# interface.net
KiCad netlist of a schematic drawn in Altium Designer
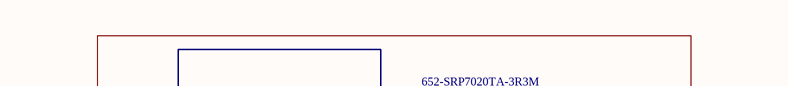
[diagram p0: interface.SchDoc, top left]
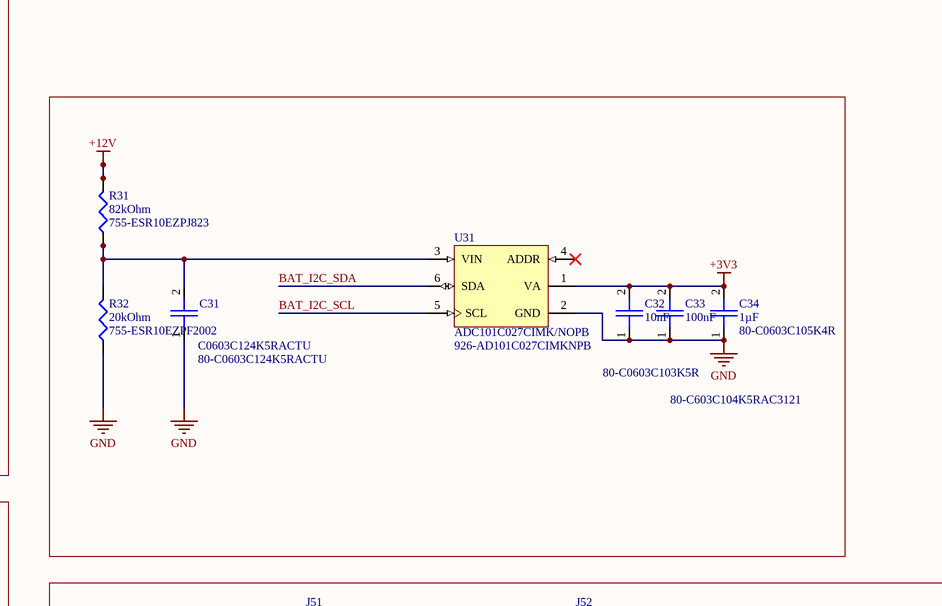
[diagram p1: interface.SchDoc, top right]
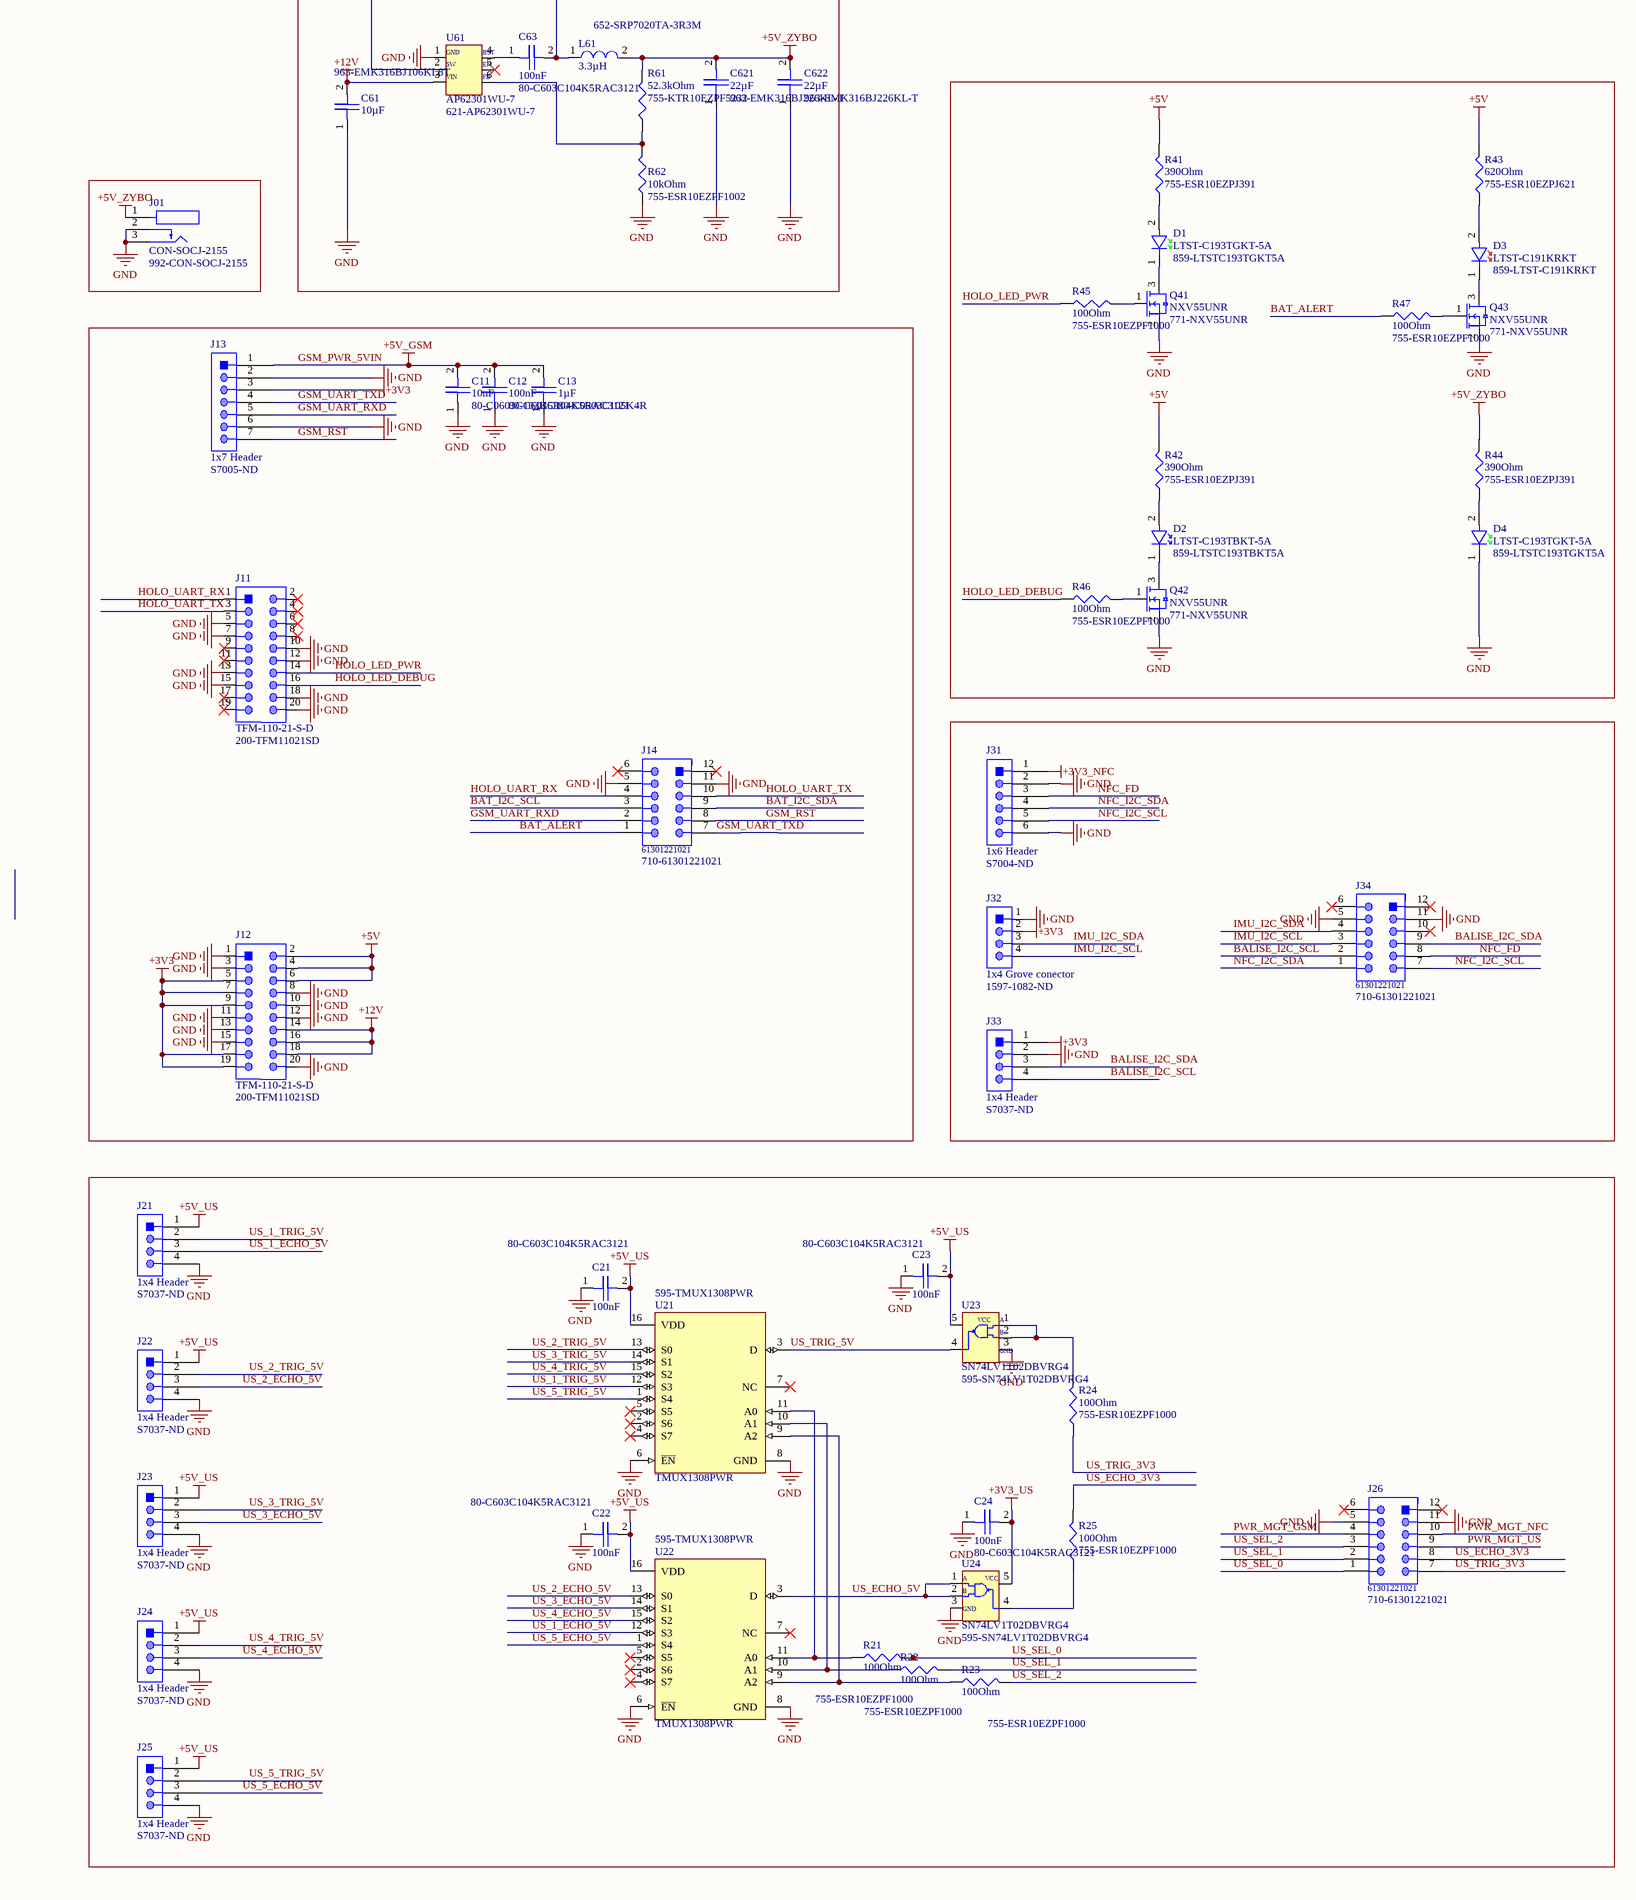
[diagram p2: interface.SchDoc, bottom left]
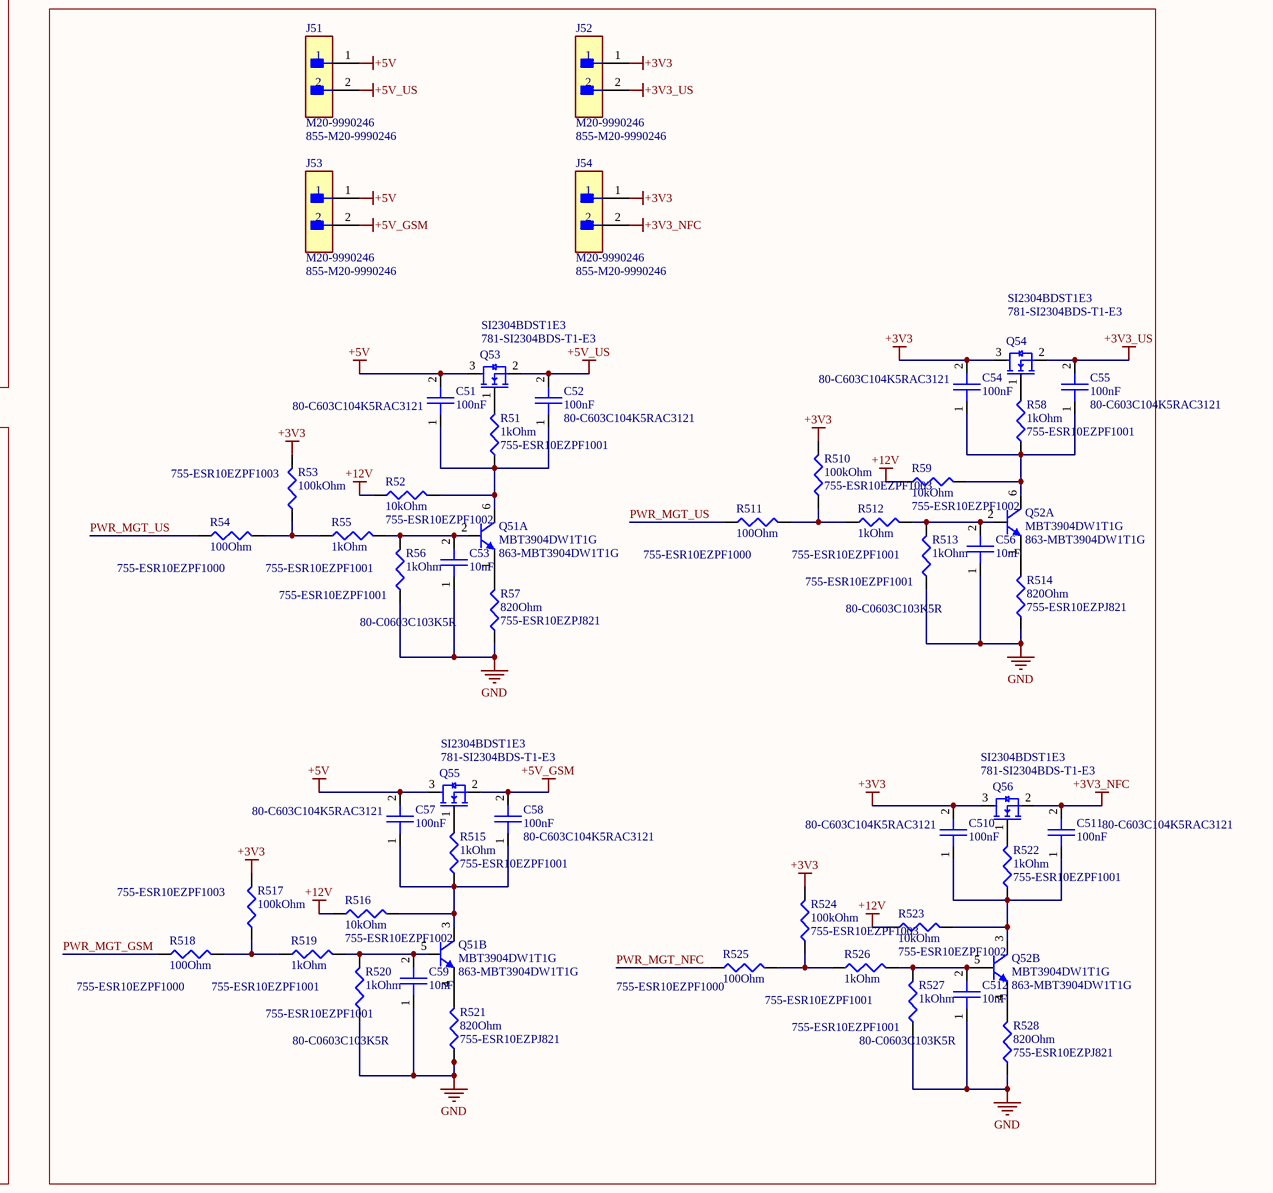
[diagram p3: interface.SchDoc, bottom right]

(export (version "E")
  (design (tool "Eeschema 10.0.6"))
  (components
    (comp (ref "C11")
      (value "10nF")
      (footprint "FP-C0603C-CF-IPC_A")
      (description "CAP CER 10000PF 50V X7R 0603")
      (fields
        (field (name "MANUFACTURER") "KEMET")
        (field (name "MANUFACTURER PART NUMBER") "C0603C103K5RACTU")
        (field (name "SUPPLIER PART NUMBER 1") "80-C0603C103K5R")
      )
      (libsource (lib "interface_Schlib") (part "C0603C103K5RACTU"))
    )
    (comp (ref "C12")
      (value "100nF")
      (footprint "FP-C0603C104K5RAC3121-IPC_A")
      (description "Cap Ceramic 0.1uF 50V X7R 10% Pad SMD 0603 125°C T/R")
      (fields
        (field (name "MANUFACTURER") "KEMET")
        (field (name "MANUFACTURER PART NUMBER") "C0603C104K5RAC3121")
        (field (name "SUPPLIER PART NUMBER 1") "80-C603C104K5RAC3121")
      )
      (libsource (lib "interface_Schlib") (part "C0603C104K5RAC3121"))
    )
    (comp (ref "C13")
      (value "1µF")
      (footprint "CAPC1608X90X35NL15T15")
      (description "Cap Ceramic 1uF 16V X7R 10% SMD 0603 125°C Paper T/R")
      (fields
        (field (name "MANUFACTURER") "KEMET")
        (field (name "MANUFACTURER PART NUMBER") "C0603C105K4RACTU")
        (field (name "SUPPLIER PART NUMBER 1") "80-C0603C105K4R")
      )
      (libsource (lib "interface_Schlib") (part "C0603C105K4RACTU"))
    )
    (comp (ref "C21")
      (value "100nF")
      (footprint "FP-C0603C104K5RAC3121-IPC_A")
      (description "Cap Ceramic 0.1uF 50V X7R 10% Pad SMD 0603 125°C T/R")
      (fields
        (field (name "MANUFACTURER") "KEMET")
        (field (name "MANUFACTURER PART NUMBER") "C0603C104K5RAC3121")
        (field (name "SUPPLIER PART NUMBER 1") "80-C603C104K5RAC3121")
      )
      (libsource (lib "interface_Schlib") (part "C0603C104K5RAC3121"))
    )
    (comp (ref "C22")
      (value "100nF")
      (footprint "FP-C0603C104K5RAC3121-IPC_A")
      (description "Cap Ceramic 0.1uF 50V X7R 10% Pad SMD 0603 125°C T/R")
      (fields
        (field (name "MANUFACTURER") "KEMET")
        (field (name "MANUFACTURER PART NUMBER") "C0603C104K5RAC3121")
        (field (name "SUPPLIER PART NUMBER 1") "80-C603C104K5RAC3121")
      )
      (libsource (lib "interface_Schlib") (part "C0603C104K5RAC3121"))
    )
    (comp (ref "C23")
      (value "100nF")
      (footprint "FP-C0603C104K5RAC3121-IPC_A")
      (description "Cap Ceramic 0.1uF 50V X7R 10% Pad SMD 0603 125°C T/R")
      (fields
        (field (name "MANUFACTURER") "KEMET")
        (field (name "MANUFACTURER PART NUMBER") "C0603C104K5RAC3121")
        (field (name "SUPPLIER PART NUMBER 1") "80-C603C104K5RAC3121")
      )
      (libsource (lib "interface_Schlib") (part "C0603C104K5RAC3121"))
    )
    (comp (ref "C24")
      (value "100nF")
      (footprint "FP-C0603C104K5RAC3121-IPC_A")
      (description "Cap Ceramic 0.1uF 50V X7R 10% Pad SMD 0603 125°C T/R")
      (fields
        (field (name "MANUFACTURER") "KEMET")
        (field (name "MANUFACTURER PART NUMBER") "C0603C104K5RAC3121")
        (field (name "SUPPLIER PART NUMBER 1") "80-C603C104K5RAC3121")
      )
      (libsource (lib "interface_Schlib") (part "C0603C104K5RAC3121"))
    )
    (comp (ref "C31")
      (value "C0603C124K5RACTU")
      (footprint "FP-C0603C-CF-IPC_A")
      (description "0603 C 120nF Ceramic Multilayer Capacitor; 50 V; +125degC; X7R Dielec; +/-10%")
      (fields
        (field (name "MANUFACTURER") "KEMET")
        (field (name "TOLERANCE") "10%")
        (field (name "SUPPLIER PART NUMBER 1") "80-C0603C124K5RACTU")
      )
      (libsource (lib "interface_Schlib") (part "C0603C124K5RACTU"))
    )
    (comp (ref "C32")
      (value "10nF")
      (footprint "FP-C0603C-CF-IPC_A")
      (description "CAP CER 10000PF 50V X7R 0603")
      (fields
        (field (name "MANUFACTURER") "KEMET")
        (field (name "MANUFACTURER PART NUMBER") "C0603C103K5RACTU")
        (field (name "SUPPLIER PART NUMBER 1") "80-C0603C103K5R")
      )
      (libsource (lib "interface_Schlib") (part "C0603C103K5RACTU"))
    )
    (comp (ref "C33")
      (value "100nF")
      (footprint "FP-C0603C104K5RAC3121-IPC_A")
      (description "Cap Ceramic 0.1uF 50V X7R 10% Pad SMD 0603 125°C T/R")
      (fields
        (field (name "MANUFACTURER") "KEMET")
        (field (name "MANUFACTURER PART NUMBER") "C0603C104K5RAC3121")
        (field (name "SUPPLIER PART NUMBER 1") "80-C603C104K5RAC3121")
      )
      (libsource (lib "interface_Schlib") (part "C0603C104K5RAC3121"))
    )
    (comp (ref "C34")
      (value "1µF")
      (footprint "CAPC1608X90X35NL15T15")
      (description "Cap Ceramic 1uF 16V X7R 10% SMD 0603 125°C Paper T/R")
      (fields
        (field (name "MANUFACTURER") "KEMET")
        (field (name "MANUFACTURER PART NUMBER") "C0603C105K4RACTU")
        (field (name "SUPPLIER PART NUMBER 1") "80-C0603C105K4R")
      )
      (libsource (lib "interface_Schlib") (part "C0603C105K4RACTU"))
    )
    (comp (ref "C51")
      (value "100nF")
      (footprint "FP-C0603C104K5RAC3121-IPC_A")
      (description "Cap Ceramic 0.1uF 50V X7R 10% Pad SMD 0603 125°C T/R")
      (fields
        (field (name "MANUFACTURER") "KEMET")
        (field (name "MANUFACTURER PART NUMBER") "C0603C104K5RAC3121")
        (field (name "SUPPLIER PART NUMBER 1") "80-C603C104K5RAC3121")
      )
      (libsource (lib "interface_Schlib") (part "C0603C104K5RAC3121"))
    )
    (comp (ref "C52")
      (value "100nF")
      (footprint "FP-C0603C104K5RAC3121-IPC_A")
      (description "Cap Ceramic 0.1uF 50V X7R 10% Pad SMD 0603 125°C T/R")
      (fields
        (field (name "MANUFACTURER") "KEMET")
        (field (name "MANUFACTURER PART NUMBER") "C0603C104K5RAC3121")
        (field (name "SUPPLIER PART NUMBER 1") "80-C603C104K5RAC3121")
      )
      (libsource (lib "interface_Schlib") (part "C0603C104K5RAC3121"))
    )
    (comp (ref "C53")
      (value "10nF")
      (footprint "FP-C0603C-CF-IPC_A")
      (description "CAP CER 10000PF 50V X7R 0603")
      (fields
        (field (name "MANUFACTURER") "KEMET")
        (field (name "MANUFACTURER PART NUMBER") "C0603C103K5RACTU")
        (field (name "SUPPLIER PART NUMBER 1") "80-C0603C103K5R")
      )
      (libsource (lib "interface_Schlib") (part "C0603C103K5RACTU"))
    )
    (comp (ref "C54")
      (value "100nF")
      (footprint "FP-C0603C104K5RAC3121-IPC_A")
      (description "Cap Ceramic 0.1uF 50V X7R 10% Pad SMD 0603 125°C T/R")
      (fields
        (field (name "MANUFACTURER") "KEMET")
        (field (name "MANUFACTURER PART NUMBER") "C0603C104K5RAC3121")
        (field (name "SUPPLIER PART NUMBER 1") "80-C603C104K5RAC3121")
      )
      (libsource (lib "interface_Schlib") (part "C0603C104K5RAC3121"))
    )
    (comp (ref "C55")
      (value "100nF")
      (footprint "FP-C0603C104K5RAC3121-IPC_A")
      (description "Cap Ceramic 0.1uF 50V X7R 10% Pad SMD 0603 125°C T/R")
      (fields
        (field (name "MANUFACTURER") "KEMET")
        (field (name "MANUFACTURER PART NUMBER") "C0603C104K5RAC3121")
        (field (name "SUPPLIER PART NUMBER 1") "80-C603C104K5RAC3121")
      )
      (libsource (lib "interface_Schlib") (part "C0603C104K5RAC3121"))
    )
    (comp (ref "C56")
      (value "10nF")
      (footprint "FP-C0603C-CF-IPC_A")
      (description "CAP CER 10000PF 50V X7R 0603")
      (fields
        (field (name "MANUFACTURER") "KEMET")
        (field (name "MANUFACTURER PART NUMBER") "C0603C103K5RACTU")
        (field (name "SUPPLIER PART NUMBER 1") "80-C0603C103K5R")
      )
      (libsource (lib "interface_Schlib") (part "C0603C103K5RACTU"))
    )
    (comp (ref "C57")
      (value "100nF")
      (footprint "FP-C0603C104K5RAC3121-IPC_A")
      (description "Cap Ceramic 0.1uF 50V X7R 10% Pad SMD 0603 125°C T/R")
      (fields
        (field (name "MANUFACTURER") "KEMET")
        (field (name "MANUFACTURER PART NUMBER") "C0603C104K5RAC3121")
        (field (name "SUPPLIER PART NUMBER 1") "80-C603C104K5RAC3121")
      )
      (libsource (lib "interface_Schlib") (part "C0603C104K5RAC3121"))
    )
    (comp (ref "C58")
      (value "100nF")
      (footprint "FP-C0603C104K5RAC3121-IPC_A")
      (description "Cap Ceramic 0.1uF 50V X7R 10% Pad SMD 0603 125°C T/R")
      (fields
        (field (name "MANUFACTURER") "KEMET")
        (field (name "MANUFACTURER PART NUMBER") "C0603C104K5RAC3121")
        (field (name "SUPPLIER PART NUMBER 1") "80-C603C104K5RAC3121")
      )
      (libsource (lib "interface_Schlib") (part "C0603C104K5RAC3121"))
    )
    (comp (ref "C59")
      (value "10nF")
      (footprint "FP-C0603C-CF-IPC_A")
      (description "CAP CER 10000PF 50V X7R 0603")
      (fields
        (field (name "MANUFACTURER") "KEMET")
        (field (name "MANUFACTURER PART NUMBER") "C0603C103K5RACTU")
        (field (name "SUPPLIER PART NUMBER 1") "80-C0603C103K5R")
      )
      (libsource (lib "interface_Schlib") (part "C0603C103K5RACTU"))
    )
    (comp (ref "C61")
      (value "10µF")
      (footprint "FP-1206-L_3_2_0_15-W_1_6-IPC_A")
      (description "Capacitor Ceramic 10uF 16V X5R 10% SMD 1206 85°C Embossed T/R")
      (fields
        (field (name "MANUFACTURER") "Taiyo Yuden")
        (field (name "MANUFACTURER PART NUMBER") "EMK316BJ106KL8T")
        (field (name "SUPPLIER PART NUMBER 1") "963-EMK316BJ106KL8T")
      )
      (libsource (lib "interface_Schlib") (part "EMK316BJ106KL8T"))
    )
    (comp (ref "C63")
      (value "100nF")
      (footprint "FP-C0603C104K5RAC3121-IPC_A")
      (description "Cap Ceramic 0.1uF 50V X7R 10% Pad SMD 0603 125°C T/R")
      (fields
        (field (name "MANUFACTURER") "KEMET")
        (field (name "MANUFACTURER PART NUMBER") "C0603C104K5RAC3121")
        (field (name "SUPPLIER PART NUMBER 1") "80-C603C104K5RAC3121")
      )
      (libsource (lib "interface_Schlib") (part "C0603C104K5RAC3121"))
    )
    (comp (ref "C510")
      (value "100nF")
      (footprint "FP-C0603C104K5RAC3121-IPC_A")
      (description "Cap Ceramic 0.1uF 50V X7R 10% Pad SMD 0603 125°C T/R")
      (fields
        (field (name "MANUFACTURER") "KEMET")
        (field (name "MANUFACTURER PART NUMBER") "C0603C104K5RAC3121")
        (field (name "SUPPLIER PART NUMBER 1") "80-C603C104K5RAC3121")
      )
      (libsource (lib "interface_Schlib") (part "C0603C104K5RAC3121"))
    )
    (comp (ref "C511")
      (value "100nF")
      (footprint "FP-C0603C104K5RAC3121-IPC_A")
      (description "Cap Ceramic 0.1uF 50V X7R 10% Pad SMD 0603 125°C T/R")
      (fields
        (field (name "MANUFACTURER") "KEMET")
        (field (name "MANUFACTURER PART NUMBER") "C0603C104K5RAC3121")
        (field (name "SUPPLIER PART NUMBER 1") "80-C603C104K5RAC3121")
      )
      (libsource (lib "interface_Schlib") (part "C0603C104K5RAC3121"))
    )
    (comp (ref "C512")
      (value "10nF")
      (footprint "FP-C0603C-CF-IPC_A")
      (description "CAP CER 10000PF 50V X7R 0603")
      (fields
        (field (name "MANUFACTURER") "KEMET")
        (field (name "MANUFACTURER PART NUMBER") "C0603C103K5RACTU")
        (field (name "SUPPLIER PART NUMBER 1") "80-C0603C103K5R")
      )
      (libsource (lib "interface_Schlib") (part "C0603C103K5RACTU"))
    )
    (comp (ref "C621")
      (value "22µF")
      (footprint "CAPC3216X180N")
      (description "Cap Ceramic 22uF 16V X7R 10% SMD 0805 125°C Paper T/R")
      (fields
        (field (name "MANUFACTURER") "Taiyo Yuden")
        (field (name "MANUFACTURER PART NUMBER") "EMK316BJ226KL-T")
        (field (name "SUPPLIER PART NUMBER 1") "963-EMK316BJ226KL-T")
      )
      (libsource (lib "interface_Schlib") (part "EMK316BJ226KL-T"))
    )
    (comp (ref "C622")
      (value "22µF")
      (footprint "CAPC3216X180N")
      (description "Cap Ceramic 22uF 16V X7R 10% SMD 0805 125°C Paper T/R")
      (fields
        (field (name "MANUFACTURER") "Taiyo Yuden")
        (field (name "MANUFACTURER PART NUMBER") "EMK316BJ226KL-T")
        (field (name "SUPPLIER PART NUMBER 1") "963-EMK316BJ226KL-T")
      )
      (libsource (lib "interface_Schlib") (part "EMK316BJ226KL-T"))
    )
    (comp (ref "D1")
      (value "LTST-C193TGKT-5A")
      (footprint "FP-LTST-C193TGKT-5A")
      (description "0603(H=0.35mm) 绿色 λD=520nm~535nm VR=5V VF=2.5V~3.1V IF=5mA PD=76mW")
      (fields
        (field (name "MANUFACTURER") "Vishay Lite-On")
        (field (name "SUPPLIER PART NUMBER 1") "859-LTSTC193TGKT5A")
      )
      (libsource (lib "interface_Schlib") (part "LTST-C193TGKT-5A"))
    )
    (comp (ref "D2")
      (value "LTST-C193TBKT-5A")
      (footprint "FP-LTST-C193TBKT-5A-MFG")
      (description "0603(H=0.35mm) 蓝色 λD=465nm~475nm VR=5V VF=2.65V~3.05V IF=5mA PD=76mW")
      (fields
        (field (name "MANUFACTURER") "Vishay Lite-On")
        (field (name "SUPPLIER PART NUMBER 1") "859-LTSTC193TBKT5A")
      )
      (libsource (lib "interface_Schlib") (part "LTST-C193TBKT-5A"))
    )
    (comp (ref "D3")
      (value "LTST-C191KRKT")
      (footprint "FP-LTST-C191KRKT")
      (description "0603(H=0.65mm) 红色 λD=631nm VR=5V VF=2.0V~2.4V IF=20mA PD=75mW")
      (fields
        (field (name "MANUFACTURER") "Vishay Lite-On")
        (field (name "SUPPLIER PART NUMBER 1") "859-LTST-C191KRKT")
        (field (name "VOLTAGE") "2V")
      )
      (libsource (lib "interface_Schlib") (part "LTST-C191KRKT"))
    )
    (comp (ref "D4")
      (value "LTST-C193TGKT-5A")
      (footprint "FP-LTST-C193TGKT-5A")
      (description "0603(H=0.35mm) 绿色 λD=520nm~535nm VR=5V VF=2.5V~3.1V IF=5mA PD=76mW")
      (fields
        (field (name "MANUFACTURER") "Vishay Lite-On")
        (field (name "SUPPLIER PART NUMBER 1") "859-LTSTC193TGKT5A")
      )
      (libsource (lib "interface_Schlib") (part "LTST-C193TGKT-5A"))
    )
    (comp (ref "J01")
      (value "CON-SOCJ-2155")
      (footprint "GRAVITECH_CON-SOCJ-2155")
      (description "DC Power Connectors Power Jack/Connector 2.1mm x 5.5mm")
      (fields
        (field (name "MANUFACTURER") "Gravitech")
        (field (name "SUPPLIER PART NUMBER 1") "992-CON-SOCJ-2155")
      )
      (libsource (lib "interface_Schlib") (part "CON-SOCJ-2155"))
    )
    (comp (ref "J11")
      (value "TFM-110-21-S-D")
      (footprint "SAMTEC_TFM-110-21-S-D")
      (fields (field (name "MANUFACTURER") "Samtec") (field (name "SUPPLIER PART NUMBER 1") "200-TFM11021SD"))
      (libsource (lib "interface_Schlib") (part "TFM-110-21-S-D"))
    )
    (comp (ref "J12")
      (value "TFM-110-21-S-D")
      (footprint "SAMTEC_TFM-110-21-S-D")
      (fields (field (name "MANUFACTURER") "Samtec") (field (name "SUPPLIER PART NUMBER 1") "200-TFM11021SD"))
      (libsource (lib "interface_Schlib") (part "TFM-110-21-S-D"))
    )
    (comp (ref "J13")
      (value "1x7 Header")
      (footprint "header 1x7")
      (description "Female, 7C, Straight, .100\"CC; 3.20mm Tail, No Mt. 100u\" Tin; PBT, Phos Bronze, 105 C")
      (fields
        (field (name "MANUFACTURER") "Sullins")
        (field (name "MANUFACTURER PART NUMBER") "PPTC071LFBN-RC")
        (field (name "SUPPLIER PART NUMBER 1") "S7005-ND")
      )
      (libsource (lib "interface_Schlib") (part "PPTC071LFBN-RC"))
    )
    (comp (ref "J14")
      (value "61301221021")
      (footprint "61301221021")
      (description "THT Angled Pin Header WR-PHD, Pitch 2.54 mm, Dual Row, 12 pins")
      (fields
        (field (name "MANUFACTURER") "Wurth Elektronik")
        (field (name "SUPPLIER PART NUMBER 1") "710-61301221021")
        (field (name "PUBLISHER") "WurthElektronik")
      )
      (libsource (lib "interface_Schlib") (part "61301221021"))
    )
    (comp (ref "J21")
      (value "1x4 Header")
      (footprint "header 1x4")
      (description "4 Positions Embase Connecteur 0,100 po (2,54mm) Trou traversant Or")
      (fields
        (field (name "MANUFACTURER") "Sullins")
        (field (name "MANUFACTURER PART NUMBER") "PPPC041LFBN-RC")
        (field (name "SUPPLIER PART NUMBER 1") "S7037-ND")
      )
      (libsource (lib "interface_Schlib") (part "PPPC041LFBN-RC"))
    )
    (comp (ref "J22")
      (value "1x4 Header")
      (footprint "header 1x4")
      (description "4 Positions Embase Connecteur 0,100 po (2,54mm) Trou traversant Or")
      (fields
        (field (name "MANUFACTURER") "Sullins")
        (field (name "MANUFACTURER PART NUMBER") "PPPC041LFBN-RC")
        (field (name "SUPPLIER PART NUMBER 1") "S7037-ND")
      )
      (libsource (lib "interface_Schlib") (part "PPPC041LFBN-RC"))
    )
    (comp (ref "J23")
      (value "1x4 Header")
      (footprint "header 1x4")
      (description "4 Positions Embase Connecteur 0,100 po (2,54mm) Trou traversant Or")
      (fields
        (field (name "MANUFACTURER") "Sullins")
        (field (name "MANUFACTURER PART NUMBER") "PPPC041LFBN-RC")
        (field (name "SUPPLIER PART NUMBER 1") "S7037-ND")
      )
      (libsource (lib "interface_Schlib") (part "PPPC041LFBN-RC"))
    )
    (comp (ref "J24")
      (value "1x4 Header")
      (footprint "header 1x4")
      (description "4 Positions Embase Connecteur 0,100 po (2,54mm) Trou traversant Or")
      (fields
        (field (name "MANUFACTURER") "Sullins")
        (field (name "MANUFACTURER PART NUMBER") "PPPC041LFBN-RC")
        (field (name "SUPPLIER PART NUMBER 1") "S7037-ND")
      )
      (libsource (lib "interface_Schlib") (part "PPPC041LFBN-RC"))
    )
    (comp (ref "J25")
      (value "1x4 Header")
      (footprint "header 1x4")
      (description "4 Positions Embase Connecteur 0,100 po (2,54mm) Trou traversant Or")
      (fields
        (field (name "MANUFACTURER") "Sullins")
        (field (name "MANUFACTURER PART NUMBER") "PPPC041LFBN-RC")
        (field (name "SUPPLIER PART NUMBER 1") "S7037-ND")
      )
      (libsource (lib "interface_Schlib") (part "PPPC041LFBN-RC"))
    )
    (comp (ref "J26")
      (value "61301221021")
      (footprint "61301221021")
      (description "THT Angled Pin Header WR-PHD, Pitch 2.54 mm, Dual Row, 12 pins")
      (fields
        (field (name "MANUFACTURER") "Wurth Elektronik")
        (field (name "SUPPLIER PART NUMBER 1") "710-61301221021")
        (field (name "PUBLISHER") "WurthElektronik")
      )
      (libsource (lib "interface_Schlib") (part "61301221021"))
    )
    (comp (ref "J31")
      (value "1x6 Header")
      (footprint "header 1x6")
      (description "Female, 6 C, Straight, .100\"CC; 3.20mm Tail, No Mt. 100u\" Tin; PBT, Phos Bronze, 105 C")
      (fields
        (field (name "MANUFACTURER") "Sullins")
        (field (name "MANUFACTURER PART NUMBER") "PPTC061LFBN-RC")
        (field (name "SUPPLIER PART NUMBER 1") "S7004-ND")
      )
      (libsource (lib "interface_Schlib") (part "PPTC061LFBN-RC"))
    )
    (comp (ref "J32")
      (value "1x4 Grove conector")
      (footprint "FP-110990030")
      (description "Grove - Universal 4 pin connector [Seeed Studio] 110990030 Grove - Universal 4 pin connector")
      (fields
        (field (name "MANUFACTURER") "Seeed Studio")
        (field (name "MANUFACTURER PART NUMBER") "110990030")
        (field (name "SUPPLIER PART NUMBER 1") "1597-1082-ND")
      )
      (libsource (lib "interface_Schlib") (part "110990030"))
    )
    (comp (ref "J33")
      (value "1x4 Header")
      (footprint "header 1x4")
      (description "4 Positions Embase Connecteur 0,100 po (2,54mm) Trou traversant Or")
      (fields
        (field (name "MANUFACTURER") "Sullins")
        (field (name "MANUFACTURER PART NUMBER") "PPPC041LFBN-RC")
        (field (name "SUPPLIER PART NUMBER 1") "S7037-ND")
      )
      (libsource (lib "interface_Schlib") (part "PPPC041LFBN-RC"))
    )
    (comp (ref "J34")
      (value "61301221021")
      (footprint "61301221021")
      (description "THT Angled Pin Header WR-PHD, Pitch 2.54 mm, Dual Row, 12 pins")
      (fields
        (field (name "MANUFACTURER") "Wurth Elektronik")
        (field (name "SUPPLIER PART NUMBER 1") "710-61301221021")
        (field (name "PUBLISHER") "WurthElektronik")
      )
      (libsource (lib "interface_Schlib") (part "61301221021"))
    )
    (comp (ref "J51")
      (value "M20-9990246")
      (footprint "FP-M20-9990246-MFG")
      (description "2.54mm (0.1\") Pitch SIL Vertical PC Tail Pin Header, 6.1mm mating pin height, tin, 2 contacts")
      (fields
        (field (name "MANUFACTURER") "Harwin")
        (field (name "SUPPLIER PART NUMBER 1") "855-M20-9990246")
      )
      (libsource (lib "interface_Schlib") (part "M20-9990246"))
    )
    (comp (ref "J52")
      (value "M20-9990246")
      (footprint "FP-M20-9990246-MFG")
      (description "2.54mm (0.1\") Pitch SIL Vertical PC Tail Pin Header, 6.1mm mating pin height, tin, 2 contacts")
      (fields
        (field (name "MANUFACTURER") "Harwin")
        (field (name "SUPPLIER PART NUMBER 1") "855-M20-9990246")
      )
      (libsource (lib "interface_Schlib") (part "M20-9990246"))
    )
    (comp (ref "J53")
      (value "M20-9990246")
      (footprint "FP-M20-9990246-MFG")
      (description "2.54mm (0.1\") Pitch SIL Vertical PC Tail Pin Header, 6.1mm mating pin height, tin, 2 contacts")
      (fields
        (field (name "MANUFACTURER") "Harwin")
        (field (name "SUPPLIER PART NUMBER 1") "855-M20-9990246")
      )
      (libsource (lib "interface_Schlib") (part "M20-9990246"))
    )
    (comp (ref "J54")
      (value "M20-9990246")
      (footprint "FP-M20-9990246-MFG")
      (description "2.54mm (0.1\") Pitch SIL Vertical PC Tail Pin Header, 6.1mm mating pin height, tin, 2 contacts")
      (fields
        (field (name "MANUFACTURER") "Harwin")
        (field (name "SUPPLIER PART NUMBER 1") "855-M20-9990246")
      )
      (libsource (lib "interface_Schlib") (part "M20-9990246"))
    )
    (comp (ref "L61")
      (value "3.3µH")
      (footprint "INDC7066X20N")
      (fields
        (field (name "MANUFACTURER") "Bourns")
        (field (name "MANUFACTURER PART NUMBER") "SRP7020TA-3R3M")
        (field (name "SUPPLIER PART NUMBER 1") "652-SRP7020TA-3R3M")
      )
      (libsource (lib "interface_Schlib") (part "SRP7020TA-3R3M"))
    )
    (comp (ref "Q41")
      (value "NXV55UNR")
      (footprint "SOT95P230X110-3N")
      (description "Transistor MOSFET N-Channel 30V 2.3A 3-Pin SOT-23")
      (fields (field (name "MANUFACTURER") "Nexperia") (field (name "SUPPLIER PART NUMBER 1") "771-NXV55UNR"))
      (libsource (lib "interface_Schlib") (part "NXV55UNR"))
    )
    (comp (ref "Q42")
      (value "NXV55UNR")
      (footprint "SOT95P230X110-3N")
      (description "Transistor MOSFET N-Channel 30V 2.3A 3-Pin SOT-23")
      (fields (field (name "MANUFACTURER") "Nexperia") (field (name "SUPPLIER PART NUMBER 1") "771-NXV55UNR"))
      (libsource (lib "interface_Schlib") (part "NXV55UNR"))
    )
    (comp (ref "Q43")
      (value "NXV55UNR")
      (footprint "SOT95P230X110-3N")
      (description "Transistor MOSFET N-Channel 30V 2.3A 3-Pin SOT-23")
      (fields (field (name "MANUFACTURER") "Nexperia") (field (name "SUPPLIER PART NUMBER 1") "771-NXV55UNR"))
      (libsource (lib "interface_Schlib") (part "NXV55UNR"))
    )
    (comp (ref "Q51")
      (value "MBT3904DW1T1G")
      (footprint "ONSC-SOT-363-6-419B-02_W_V")
      (description "Dual General Purpose Transistors, 6-Pin SOT-363, Pb-Free, Tape and Reel")
      (fields
        (field (name "MANUFACTURER") "On Semiconductor")
        (field (name "SUPPLIER PART NUMBER 1") "863-MBT3904DW1T1G")
      )
      (libsource (lib "interface_Schlib") (part "CMP-1048-00877-1"))
    )
    (comp (ref "Q52")
      (value "MBT3904DW1T1G")
      (footprint "ONSC-SOT-363-6-419B-02_W_V")
      (description "Dual General Purpose Transistors, 6-Pin SOT-363, Pb-Free, Tape and Reel")
      (fields
        (field (name "MANUFACTURER") "On Semiconductor")
        (field (name "SUPPLIER PART NUMBER 1") "863-MBT3904DW1T1G")
      )
      (libsource (lib "interface_Schlib") (part "CMP-1048-00877-1"))
    )
    (comp (ref "Q53")
      (value "SI2304BDST1E3")
      (footprint "FP-SI2304BDST1E3")
      (description "Single N-Channel 30 V 0.07 Ohms Surface Mount Power Mosfet - SOT-23")
      (fields
        (field (name "MANUFACTURER") "Vishay")
        (field (name "SUPPLIER PART NUMBER 1") "781-SI2304BDS-T1-E3")
      )
      (libsource (lib "interface_Schlib") (part "SI2304BDST1E3"))
    )
    (comp (ref "Q54")
      (value "SI2304BDST1E3")
      (footprint "FP-SI2304BDST1E3")
      (description "Single N-Channel 30 V 0.07 Ohms Surface Mount Power Mosfet - SOT-23")
      (fields
        (field (name "MANUFACTURER") "Vishay")
        (field (name "SUPPLIER PART NUMBER 1") "781-SI2304BDS-T1-E3")
      )
      (libsource (lib "interface_Schlib") (part "SI2304BDST1E3"))
    )
    (comp (ref "Q55")
      (value "SI2304BDST1E3")
      (footprint "FP-SI2304BDST1E3")
      (description "Single N-Channel 30 V 0.07 Ohms Surface Mount Power Mosfet - SOT-23")
      (fields
        (field (name "MANUFACTURER") "Vishay")
        (field (name "SUPPLIER PART NUMBER 1") "781-SI2304BDS-T1-E3")
      )
      (libsource (lib "interface_Schlib") (part "SI2304BDST1E3"))
    )
    (comp (ref "Q56")
      (value "SI2304BDST1E3")
      (footprint "FP-SI2304BDST1E3")
      (description "Single N-Channel 30 V 0.07 Ohms Surface Mount Power Mosfet - SOT-23")
      (fields
        (field (name "MANUFACTURER") "Vishay")
        (field (name "SUPPLIER PART NUMBER 1") "781-SI2304BDS-T1-E3")
      )
      (libsource (lib "interface_Schlib") (part "SI2304BDST1E3"))
    )
    (comp (ref "R21")
      (value "100Ohm")
      (footprint "FP-ESR10-IPC_A")
      (description "Res Thick Film 0805 100 Ohm 1% 2/5W ±100ppm/°C Molded SMD Paper T/R")
      (fields
        (field (name "MANUFACTURER") "Rohm")
        (field (name "MANUFACTURER PART NUMBER") "ESR10EZPF1000")
        (field (name "SUPPLIER PART NUMBER 1") "755-ESR10EZPF1000")
      )
      (libsource (lib "interface_Schlib") (part "ESR10EZPF1000"))
    )
    (comp (ref "R22")
      (value "100Ohm")
      (footprint "FP-ESR10-IPC_A")
      (description "Res Thick Film 0805 100 Ohm 1% 2/5W ±100ppm/°C Molded SMD Paper T/R")
      (fields
        (field (name "MANUFACTURER") "Rohm")
        (field (name "MANUFACTURER PART NUMBER") "ESR10EZPF1000")
        (field (name "SUPPLIER PART NUMBER 1") "755-ESR10EZPF1000")
      )
      (libsource (lib "interface_Schlib") (part "ESR10EZPF1000"))
    )
    (comp (ref "R23")
      (value "100Ohm")
      (footprint "FP-ESR10-IPC_A")
      (description "Res Thick Film 0805 100 Ohm 1% 2/5W ±100ppm/°C Molded SMD Paper T/R")
      (fields
        (field (name "MANUFACTURER") "Rohm")
        (field (name "MANUFACTURER PART NUMBER") "ESR10EZPF1000")
        (field (name "SUPPLIER PART NUMBER 1") "755-ESR10EZPF1000")
      )
      (libsource (lib "interface_Schlib") (part "ESR10EZPF1000"))
    )
    (comp (ref "R24")
      (value "100Ohm")
      (footprint "FP-ESR10-IPC_A")
      (description "Res Thick Film 0805 100 Ohm 1% 2/5W ±100ppm/°C Molded SMD Paper T/R")
      (fields
        (field (name "MANUFACTURER") "Rohm")
        (field (name "MANUFACTURER PART NUMBER") "ESR10EZPF1000")
        (field (name "SUPPLIER PART NUMBER 1") "755-ESR10EZPF1000")
      )
      (libsource (lib "interface_Schlib") (part "ESR10EZPF1000"))
    )
    (comp (ref "R25")
      (value "100Ohm")
      (footprint "FP-ESR10-IPC_A")
      (description "Res Thick Film 0805 100 Ohm 1% 2/5W ±100ppm/°C Molded SMD Paper T/R")
      (fields
        (field (name "MANUFACTURER") "Rohm")
        (field (name "MANUFACTURER PART NUMBER") "ESR10EZPF1000")
        (field (name "SUPPLIER PART NUMBER 1") "755-ESR10EZPF1000")
      )
      (libsource (lib "interface_Schlib") (part "ESR10EZPF1000"))
    )
    (comp (ref "R31")
      (value "82kOhm")
      (footprint "FP-ESR10-IPC_A")
      (description "Res Anti-surge 0805 82K Ohm 0.4W 5% SMD")
      (fields
        (field (name "MANUFACTURER") "Rohm")
        (field (name "MANUFACTURER PART NUMBER") "ESR10EZPJ823")
        (field (name "SUPPLIER PART NUMBER 1") "755-ESR10EZPJ823")
      )
      (libsource (lib "interface_Schlib") (part "ESR10EZPJ823"))
    )
    (comp (ref "R32")
      (value "20kOhm")
      (footprint "FP-ESR10-IPC_A")
      (description "Res Thick Film 0805 20KOhm 1% 2/5W ±100ppm/°C Molded SMD Paper T/R")
      (fields
        (field (name "MANUFACTURER") "Rohm")
        (field (name "MANUFACTURER PART NUMBER") "ESR10EZPF2002")
        (field (name "SUPPLIER PART NUMBER 1") "755-ESR10EZPF2002")
      )
      (libsource (lib "interface_Schlib") (part "ESR10EZPF2002"))
    )
    (comp (ref "R41")
      (value "390Ohm")
      (footprint "FP-ESR10-IPC_A")
      (description "Res Thick Film 0805 390 Ohm 5% 0.4W ±200ppm/C Pad SMD Automotive T/R")
      (fields
        (field (name "MANUFACTURER") "Rohm")
        (field (name "MANUFACTURER PART NUMBER") "ESR10EZPJ391")
        (field (name "SUPPLIER PART NUMBER 1") "755-ESR10EZPJ391")
      )
      (libsource (lib "interface_Schlib") (part "ESR10EZPJ391"))
    )
    (comp (ref "R42")
      (value "390Ohm")
      (footprint "FP-ESR10-IPC_A")
      (description "Res Thick Film 0805 390 Ohm 5% 0.4W ±200ppm/C Pad SMD Automotive T/R")
      (fields
        (field (name "MANUFACTURER") "Rohm")
        (field (name "MANUFACTURER PART NUMBER") "ESR10EZPJ391")
        (field (name "SUPPLIER PART NUMBER 1") "755-ESR10EZPJ391")
      )
      (libsource (lib "interface_Schlib") (part "ESR10EZPJ391"))
    )
    (comp (ref "R43")
      (value "620Ohm")
      (footprint "FP-ESR10-IPC_A")
      (description "Res Thick Film 0805 620 Ohm 5% 0.4W ±200ppm/C Pad SMD Automotive T/R")
      (fields
        (field (name "MANUFACTURER") "Rohm")
        (field (name "MANUFACTURER PART NUMBER") "ESR10EZPJ621")
        (field (name "SUPPLIER PART NUMBER 1") "755-ESR10EZPJ621")
      )
      (libsource (lib "interface_Schlib") (part "ESR10EZPJ621"))
    )
    (comp (ref "R44")
      (value "390Ohm")
      (footprint "FP-ESR10-IPC_A")
      (description "Res Thick Film 0805 390 Ohm 5% 0.4W ±200ppm/C Pad SMD Automotive T/R")
      (fields
        (field (name "MANUFACTURER") "Rohm")
        (field (name "MANUFACTURER PART NUMBER") "ESR10EZPJ391")
        (field (name "SUPPLIER PART NUMBER 1") "755-ESR10EZPJ391")
      )
      (libsource (lib "interface_Schlib") (part "ESR10EZPJ391"))
    )
    (comp (ref "R45")
      (value "100Ohm")
      (footprint "FP-ESR10-IPC_A")
      (description "Res Thick Film 0805 100 Ohm 1% 2/5W ±100ppm/°C Molded SMD Paper T/R")
      (fields
        (field (name "MANUFACTURER") "Rohm")
        (field (name "MANUFACTURER PART NUMBER") "ESR10EZPF1000")
        (field (name "SUPPLIER PART NUMBER 1") "755-ESR10EZPF1000")
      )
      (libsource (lib "interface_Schlib") (part "ESR10EZPF1000"))
    )
    (comp (ref "R46")
      (value "100Ohm")
      (footprint "FP-ESR10-IPC_A")
      (description "Res Thick Film 0805 100 Ohm 1% 2/5W ±100ppm/°C Molded SMD Paper T/R")
      (fields
        (field (name "MANUFACTURER") "Rohm")
        (field (name "MANUFACTURER PART NUMBER") "ESR10EZPF1000")
        (field (name "SUPPLIER PART NUMBER 1") "755-ESR10EZPF1000")
      )
      (libsource (lib "interface_Schlib") (part "ESR10EZPF1000"))
    )
    (comp (ref "R47")
      (value "100Ohm")
      (footprint "FP-ESR10-IPC_A")
      (description "Res Thick Film 0805 100 Ohm 1% 2/5W ±100ppm/°C Molded SMD Paper T/R")
      (fields
        (field (name "MANUFACTURER") "Rohm")
        (field (name "MANUFACTURER PART NUMBER") "ESR10EZPF1000")
        (field (name "SUPPLIER PART NUMBER 1") "755-ESR10EZPF1000")
      )
      (libsource (lib "interface_Schlib") (part "ESR10EZPF1000"))
    )
    (comp (ref "R51")
      (value "1kOhm")
      (footprint "FP-ESR10-IPC_A")
      (description "Res Thick Film 0805 1K Ohm 1% 0.4W ±100ppm/C Epoxy Resin Pad SMD Automotive T/R")
      (fields
        (field (name "MANUFACTURER") "Rohm")
        (field (name "MANUFACTURER PART NUMBER") "ESR10EZPF1001")
        (field (name "SUPPLIER PART NUMBER 1") "755-ESR10EZPF1001")
      )
      (libsource (lib "interface_Schlib") (part "ESR10EZPF1001"))
    )
    (comp (ref "R52")
      (value "10kOhm")
      (footprint "FP-ESR10-IPC_A")
      (description "Res Thick Film 0805 10K Ohm 1% 0.4W ±100ppm/C Pad SMD Automotive T/R")
      (fields
        (field (name "MANUFACTURER") "Rohm")
        (field (name "MANUFACTURER PART NUMBER") "ESR10EZPF1002")
        (field (name "SUPPLIER PART NUMBER 1") "755-ESR10EZPF1002")
      )
      (libsource (lib "interface_Schlib") (part "ESR10EZPF1002"))
    )
    (comp (ref "R53")
      (value "100kOhm")
      (footprint "FP-ESR10-IPC_A")
      (description "Res Thick Film 0805 100K Ohm 1% 0.4W ±100ppm/C Epoxy Resin Pad SMD Automotive T/R")
      (fields
        (field (name "MANUFACTURER") "Rohm")
        (field (name "MANUFACTURER PART NUMBER") "ESR10EZPF1003")
        (field (name "SUPPLIER PART NUMBER 1") "755-ESR10EZPF1003")
      )
      (libsource (lib "interface_Schlib") (part "ESR10EZPF1003"))
    )
    (comp (ref "R54")
      (value "100Ohm")
      (footprint "FP-ESR10-IPC_A")
      (description "Res Thick Film 0805 100 Ohm 1% 2/5W ±100ppm/°C Molded SMD Paper T/R")
      (fields
        (field (name "MANUFACTURER") "Rohm")
        (field (name "MANUFACTURER PART NUMBER") "ESR10EZPF1000")
        (field (name "SUPPLIER PART NUMBER 1") "755-ESR10EZPF1000")
      )
      (libsource (lib "interface_Schlib") (part "ESR10EZPF1000"))
    )
    (comp (ref "R55")
      (value "1kOhm")
      (footprint "FP-ESR10-IPC_A")
      (description "Res Thick Film 0805 1K Ohm 1% 0.4W ±100ppm/C Epoxy Resin Pad SMD Automotive T/R")
      (fields
        (field (name "MANUFACTURER") "Rohm")
        (field (name "MANUFACTURER PART NUMBER") "ESR10EZPF1001")
        (field (name "SUPPLIER PART NUMBER 1") "755-ESR10EZPF1001")
      )
      (libsource (lib "interface_Schlib") (part "ESR10EZPF1001"))
    )
    (comp (ref "R56")
      (value "1kOhm")
      (footprint "FP-ESR10-IPC_A")
      (description "Res Thick Film 0805 1K Ohm 1% 0.4W ±100ppm/C Epoxy Resin Pad SMD Automotive T/R")
      (fields
        (field (name "MANUFACTURER") "Rohm")
        (field (name "MANUFACTURER PART NUMBER") "ESR10EZPF1001")
        (field (name "SUPPLIER PART NUMBER 1") "755-ESR10EZPF1001")
      )
      (libsource (lib "interface_Schlib") (part "ESR10EZPF1001"))
    )
    (comp (ref "R57")
      (value "820Ohm")
      (footprint "FP-ESR10-IPC_A")
      (description "Res Thick Film 0805 820 Ohm 5% 0.4W ±200ppm/C Epoxy Resin Pad SMD Automotive T/R")
      (fields
        (field (name "MANUFACTURER") "Rohm")
        (field (name "MANUFACTURER PART NUMBER") "ESR10EZPJ821")
        (field (name "SUPPLIER PART NUMBER 1") "755-ESR10EZPJ821")
      )
      (libsource (lib "interface_Schlib") (part "ESR10EZPJ821"))
    )
    (comp (ref "R58")
      (value "1kOhm")
      (footprint "FP-ESR10-IPC_A")
      (description "Res Thick Film 0805 1K Ohm 1% 0.4W ±100ppm/C Epoxy Resin Pad SMD Automotive T/R")
      (fields
        (field (name "MANUFACTURER") "Rohm")
        (field (name "MANUFACTURER PART NUMBER") "ESR10EZPF1001")
        (field (name "SUPPLIER PART NUMBER 1") "755-ESR10EZPF1001")
      )
      (libsource (lib "interface_Schlib") (part "ESR10EZPF1001"))
    )
    (comp (ref "R59")
      (value "10kOhm")
      (footprint "FP-ESR10-IPC_A")
      (description "Res Thick Film 0805 10K Ohm 1% 0.4W ±100ppm/C Pad SMD Automotive T/R")
      (fields
        (field (name "MANUFACTURER") "Rohm")
        (field (name "MANUFACTURER PART NUMBER") "ESR10EZPF1002")
        (field (name "SUPPLIER PART NUMBER 1") "755-ESR10EZPF1002")
      )
      (libsource (lib "interface_Schlib") (part "ESR10EZPF1002"))
    )
    (comp (ref "R61")
      (value "52.3kOhm")
      (footprint "FP-KTR10-IPC_A")
      (description "Res High Voltage 0805 52.3K Ohm 1/8W 1% SMD")
      (fields
        (field (name "MANUFACTURER") "Rohm")
        (field (name "MANUFACTURER PART NUMBER") "KTR10EZPF5232")
        (field (name "SUPPLIER PART NUMBER 1") "755-KTR10EZPF5232")
      )
      (libsource (lib "interface_Schlib") (part "KTR10EZPF5232"))
    )
    (comp (ref "R62")
      (value "10kOhm")
      (footprint "FP-ESR10-IPC_A")
      (description "Res Thick Film 0805 10K Ohm 1% 0.4W ±100ppm/C Pad SMD Automotive T/R")
      (fields
        (field (name "MANUFACTURER") "Rohm")
        (field (name "MANUFACTURER PART NUMBER") "ESR10EZPF1002")
        (field (name "SUPPLIER PART NUMBER 1") "755-ESR10EZPF1002")
      )
      (libsource (lib "interface_Schlib") (part "ESR10EZPF1002"))
    )
    (comp (ref "R510")
      (value "100kOhm")
      (footprint "FP-ESR10-IPC_A")
      (description "Res Thick Film 0805 100K Ohm 1% 0.4W ±100ppm/C Epoxy Resin Pad SMD Automotive T/R")
      (fields
        (field (name "MANUFACTURER") "Rohm")
        (field (name "MANUFACTURER PART NUMBER") "ESR10EZPF1003")
        (field (name "SUPPLIER PART NUMBER 1") "755-ESR10EZPF1003")
      )
      (libsource (lib "interface_Schlib") (part "ESR10EZPF1003"))
    )
    (comp (ref "R511")
      (value "100Ohm")
      (footprint "FP-ESR10-IPC_A")
      (description "Res Thick Film 0805 100 Ohm 1% 2/5W ±100ppm/°C Molded SMD Paper T/R")
      (fields
        (field (name "MANUFACTURER") "Rohm")
        (field (name "MANUFACTURER PART NUMBER") "ESR10EZPF1000")
        (field (name "SUPPLIER PART NUMBER 1") "755-ESR10EZPF1000")
      )
      (libsource (lib "interface_Schlib") (part "ESR10EZPF1000"))
    )
    (comp (ref "R512")
      (value "1kOhm")
      (footprint "FP-ESR10-IPC_A")
      (description "Res Thick Film 0805 1K Ohm 1% 0.4W ±100ppm/C Epoxy Resin Pad SMD Automotive T/R")
      (fields
        (field (name "MANUFACTURER") "Rohm")
        (field (name "MANUFACTURER PART NUMBER") "ESR10EZPF1001")
        (field (name "SUPPLIER PART NUMBER 1") "755-ESR10EZPF1001")
      )
      (libsource (lib "interface_Schlib") (part "ESR10EZPF1001"))
    )
    (comp (ref "R513")
      (value "1kOhm")
      (footprint "FP-ESR10-IPC_A")
      (description "Res Thick Film 0805 1K Ohm 1% 0.4W ±100ppm/C Epoxy Resin Pad SMD Automotive T/R")
      (fields
        (field (name "MANUFACTURER") "Rohm")
        (field (name "MANUFACTURER PART NUMBER") "ESR10EZPF1001")
        (field (name "SUPPLIER PART NUMBER 1") "755-ESR10EZPF1001")
      )
      (libsource (lib "interface_Schlib") (part "ESR10EZPF1001"))
    )
    (comp (ref "R514")
      (value "820Ohm")
      (footprint "FP-ESR10-IPC_A")
      (description "Res Thick Film 0805 820 Ohm 5% 0.4W ±200ppm/C Epoxy Resin Pad SMD Automotive T/R")
      (fields
        (field (name "MANUFACTURER") "Rohm")
        (field (name "MANUFACTURER PART NUMBER") "ESR10EZPJ821")
        (field (name "SUPPLIER PART NUMBER 1") "755-ESR10EZPJ821")
      )
      (libsource (lib "interface_Schlib") (part "ESR10EZPJ821"))
    )
    (comp (ref "R515")
      (value "1kOhm")
      (footprint "FP-ESR10-IPC_A")
      (description "Res Thick Film 0805 1K Ohm 1% 0.4W ±100ppm/C Epoxy Resin Pad SMD Automotive T/R")
      (fields
        (field (name "MANUFACTURER") "Rohm")
        (field (name "MANUFACTURER PART NUMBER") "ESR10EZPF1001")
        (field (name "SUPPLIER PART NUMBER 1") "755-ESR10EZPF1001")
      )
      (libsource (lib "interface_Schlib") (part "ESR10EZPF1001"))
    )
    (comp (ref "R516")
      (value "10kOhm")
      (footprint "FP-ESR10-IPC_A")
      (description "Res Thick Film 0805 10K Ohm 1% 0.4W ±100ppm/C Pad SMD Automotive T/R")
      (fields
        (field (name "MANUFACTURER") "Rohm")
        (field (name "MANUFACTURER PART NUMBER") "ESR10EZPF1002")
        (field (name "SUPPLIER PART NUMBER 1") "755-ESR10EZPF1002")
      )
      (libsource (lib "interface_Schlib") (part "ESR10EZPF1002"))
    )
    (comp (ref "R517")
      (value "100kOhm")
      (footprint "FP-ESR10-IPC_A")
      (description "Res Thick Film 0805 100K Ohm 1% 0.4W ±100ppm/C Epoxy Resin Pad SMD Automotive T/R")
      (fields
        (field (name "MANUFACTURER") "Rohm")
        (field (name "MANUFACTURER PART NUMBER") "ESR10EZPF1003")
        (field (name "SUPPLIER PART NUMBER 1") "755-ESR10EZPF1003")
      )
      (libsource (lib "interface_Schlib") (part "ESR10EZPF1003"))
    )
    (comp (ref "R518")
      (value "100Ohm")
      (footprint "FP-ESR10-IPC_A")
      (description "Res Thick Film 0805 100 Ohm 1% 2/5W ±100ppm/°C Molded SMD Paper T/R")
      (fields
        (field (name "MANUFACTURER") "Rohm")
        (field (name "MANUFACTURER PART NUMBER") "ESR10EZPF1000")
        (field (name "SUPPLIER PART NUMBER 1") "755-ESR10EZPF1000")
      )
      (libsource (lib "interface_Schlib") (part "ESR10EZPF1000"))
    )
    (comp (ref "R519")
      (value "1kOhm")
      (footprint "FP-ESR10-IPC_A")
      (description "Res Thick Film 0805 1K Ohm 1% 0.4W ±100ppm/C Epoxy Resin Pad SMD Automotive T/R")
      (fields
        (field (name "MANUFACTURER") "Rohm")
        (field (name "MANUFACTURER PART NUMBER") "ESR10EZPF1001")
        (field (name "SUPPLIER PART NUMBER 1") "755-ESR10EZPF1001")
      )
      (libsource (lib "interface_Schlib") (part "ESR10EZPF1001"))
    )
    (comp (ref "R520")
      (value "1kOhm")
      (footprint "FP-ESR10-IPC_A")
      (description "Res Thick Film 0805 1K Ohm 1% 0.4W ±100ppm/C Epoxy Resin Pad SMD Automotive T/R")
      (fields
        (field (name "MANUFACTURER") "Rohm")
        (field (name "MANUFACTURER PART NUMBER") "ESR10EZPF1001")
        (field (name "SUPPLIER PART NUMBER 1") "755-ESR10EZPF1001")
      )
      (libsource (lib "interface_Schlib") (part "ESR10EZPF1001"))
    )
    (comp (ref "R521")
      (value "820Ohm")
      (footprint "FP-ESR10-IPC_A")
      (description "Res Thick Film 0805 820 Ohm 5% 0.4W ±200ppm/C Epoxy Resin Pad SMD Automotive T/R")
      (fields
        (field (name "MANUFACTURER") "Rohm")
        (field (name "MANUFACTURER PART NUMBER") "ESR10EZPJ821")
        (field (name "SUPPLIER PART NUMBER 1") "755-ESR10EZPJ821")
      )
      (libsource (lib "interface_Schlib") (part "ESR10EZPJ821"))
    )
    (comp (ref "R522")
      (value "1kOhm")
      (footprint "FP-ESR10-IPC_A")
      (description "Res Thick Film 0805 1K Ohm 1% 0.4W ±100ppm/C Epoxy Resin Pad SMD Automotive T/R")
      (fields
        (field (name "MANUFACTURER") "Rohm")
        (field (name "MANUFACTURER PART NUMBER") "ESR10EZPF1001")
        (field (name "SUPPLIER PART NUMBER 1") "755-ESR10EZPF1001")
      )
      (libsource (lib "interface_Schlib") (part "ESR10EZPF1001"))
    )
    (comp (ref "R523")
      (value "10kOhm")
      (footprint "FP-ESR10-IPC_A")
      (description "Res Thick Film 0805 10K Ohm 1% 0.4W ±100ppm/C Pad SMD Automotive T/R")
      (fields
        (field (name "MANUFACTURER") "Rohm")
        (field (name "MANUFACTURER PART NUMBER") "ESR10EZPF1002")
        (field (name "SUPPLIER PART NUMBER 1") "755-ESR10EZPF1002")
      )
      (libsource (lib "interface_Schlib") (part "ESR10EZPF1002"))
    )
    (comp (ref "R524")
      (value "100kOhm")
      (footprint "FP-ESR10-IPC_A")
      (description "Res Thick Film 0805 100K Ohm 1% 0.4W ±100ppm/C Epoxy Resin Pad SMD Automotive T/R")
      (fields
        (field (name "MANUFACTURER") "Rohm")
        (field (name "MANUFACTURER PART NUMBER") "ESR10EZPF1003")
        (field (name "SUPPLIER PART NUMBER 1") "755-ESR10EZPF1003")
      )
      (libsource (lib "interface_Schlib") (part "ESR10EZPF1003"))
    )
    (comp (ref "R525")
      (value "100Ohm")
      (footprint "FP-ESR10-IPC_A")
      (description "Res Thick Film 0805 100 Ohm 1% 2/5W ±100ppm/°C Molded SMD Paper T/R")
      (fields
        (field (name "MANUFACTURER") "Rohm")
        (field (name "MANUFACTURER PART NUMBER") "ESR10EZPF1000")
        (field (name "SUPPLIER PART NUMBER 1") "755-ESR10EZPF1000")
      )
      (libsource (lib "interface_Schlib") (part "ESR10EZPF1000"))
    )
    (comp (ref "R526")
      (value "1kOhm")
      (footprint "FP-ESR10-IPC_A")
      (description "Res Thick Film 0805 1K Ohm 1% 0.4W ±100ppm/C Epoxy Resin Pad SMD Automotive T/R")
      (fields
        (field (name "MANUFACTURER") "Rohm")
        (field (name "MANUFACTURER PART NUMBER") "ESR10EZPF1001")
        (field (name "SUPPLIER PART NUMBER 1") "755-ESR10EZPF1001")
      )
      (libsource (lib "interface_Schlib") (part "ESR10EZPF1001"))
    )
    (comp (ref "R527")
      (value "1kOhm")
      (footprint "FP-ESR10-IPC_A")
      (description "Res Thick Film 0805 1K Ohm 1% 0.4W ±100ppm/C Epoxy Resin Pad SMD Automotive T/R")
      (fields
        (field (name "MANUFACTURER") "Rohm")
        (field (name "MANUFACTURER PART NUMBER") "ESR10EZPF1001")
        (field (name "SUPPLIER PART NUMBER 1") "755-ESR10EZPF1001")
      )
      (libsource (lib "interface_Schlib") (part "ESR10EZPF1001"))
    )
    (comp (ref "R528")
      (value "820Ohm")
      (footprint "FP-ESR10-IPC_A")
      (description "Res Thick Film 0805 820 Ohm 5% 0.4W ±200ppm/C Epoxy Resin Pad SMD Automotive T/R")
      (fields
        (field (name "MANUFACTURER") "Rohm")
        (field (name "MANUFACTURER PART NUMBER") "ESR10EZPJ821")
        (field (name "SUPPLIER PART NUMBER 1") "755-ESR10EZPJ821")
      )
      (libsource (lib "interface_Schlib") (part "ESR10EZPJ821"))
    )
    (comp (ref "U21")
      (value "TMUX1308PWR")
      (footprint "FP-PW0016A-IPC_A")
      (description "1-CHANNEL, 8:1 GENERAL-PURPOSE A")
      (fields (field (name "SUPPLIER PART NUMBER 1") "595-TMUX1308PWR"))
      (libsource (lib "interface_Schlib") (part "TMUX1308PWR"))
    )
    (comp (ref "U22")
      (value "TMUX1308PWR")
      (footprint "FP-PW0016A-IPC_A")
      (description "1-CHANNEL, 8:1 GENERAL-PURPOSE A")
      (fields (field (name "SUPPLIER PART NUMBER 1") "595-TMUX1308PWR"))
      (libsource (lib "interface_Schlib") (part "TMUX1308PWR"))
    )
    (comp (ref "U23")
      (value "SN74LV1T02DBVRG4")
      (footprint "FP-DBV0005A-IPC_A")
      (description "Single Power Supply 2-input POSITIVE NOR GATE Logic Level Shifter 5-SOT-23 -40 to 125")
      (fields
        (field (name "MANUFACTURER") "Texas Instruments")
        (field (name "SUPPLIER PART NUMBER 1") "595-SN74LV1T02DBVRG4")
      )
      (libsource (lib "") (part "SN74LV1T02DBVRG4_1"))
    )
    (comp (ref "U24")
      (value "SN74LV1T02DBVRG4")
      (footprint "FP-DBV0005A-IPC_A")
      (description "Single Power Supply 2-input POSITIVE NOR GATE Logic Level Shifter 5-SOT-23 -40 to 125")
      (fields
        (field (name "MANUFACTURER") "Texas Instruments")
        (field (name "SUPPLIER PART NUMBER 1") "595-SN74LV1T02DBVRG4")
      )
      (libsource (lib "interface_Schlib") (part "SN74LV1T02DBVRG4"))
    )
    (comp (ref "U31")
      (value "ADC101C027CIMK/NOPB")
      (footprint "MK06A_N")
      (description "10-Bit, 189kSPS, 1-Ch SAR ADC with I2C 6-SOT-23-THIN -40 to 105")
      (fields
        (field (name "MANUFACTURER") "TI National Semiconductor")
        (field (name "SUPPLIER PART NUMBER 1") "926-AD101C027CIMKNPB")
      )
      (libsource (lib "interface_Schlib") (part "ADC101C027CIMK/NOPB"))
    )
    (comp (ref "U61")
      (value "AP62301WU-7")
      (footprint "TSOP95P280X100-6N")
      (description "Converter DC to DC 4.2V to 18V Synchronous Step Down Single-Out 3A 6-Pin TSOT-26 T/R")
      (fields
        (field (name "MANUFACTURER") "Diodes")
        (field (name "SUPPLIER PART NUMBER 1") "621-AP62301WU-7")
      )
      (libsource (lib "interface_Schlib") (part "AP62301WU-7"))
    )
  )
  (nets
    (net (code "1") (name "+3V3") (class "Default")
      (node (ref "C32") (pin "2") (pinfunction "2_2") (pintype "passive"))
      (node (ref "C33") (pin "2") (pinfunction "2_2") (pintype "passive"))
      (node (ref "C34") (pin "2") (pinfunction "2_2") (pintype "passive"))
      (node (ref "C510") (pin "2") (pinfunction "2_2") (pintype "passive"))
      (node (ref "C54") (pin "2") (pinfunction "2_2") (pintype "passive"))
      (node (ref "J12") (pin "17") (pinfunction "17_17") (pintype "passive"))
      (node (ref "J12") (pin "19") (pinfunction "19_19") (pintype "passive"))
      (node (ref "J12") (pin "5") (pinfunction "5_5") (pintype "passive"))
      (node (ref "J12") (pin "7") (pinfunction "7_7") (pintype "passive"))
      (node (ref "J12") (pin "9") (pinfunction "9_9") (pintype "passive"))
      (node (ref "J13") (pin "3") (pinfunction "3_3") (pintype "passive"))
      (node (ref "J32") (pin "2") (pinfunction "2_2") (pintype "passive"))
      (node (ref "J33") (pin "1") (pinfunction "1_1") (pintype "passive"))
      (node (ref "J52") (pin "1") (pinfunction "1_1") (pintype "passive"))
      (node (ref "J54") (pin "1") (pinfunction "1_1") (pintype "passive"))
      (node (ref "Q54") (pin "3") (pinfunction "3_3") (pintype "passive"))
      (node (ref "Q56") (pin "3") (pinfunction "3_3") (pintype "passive"))
      (node (ref "R510") (pin "2") (pinfunction "2_2") (pintype "passive"))
      (node (ref "R517") (pin "2") (pinfunction "2_2") (pintype "passive"))
      (node (ref "R524") (pin "2") (pinfunction "2_2") (pintype "passive"))
      (node (ref "R53") (pin "2") (pinfunction "2_2") (pintype "passive"))
      (node (ref "U31") (pin "1") (pinfunction "VA_1") (pintype "power_in"))
    )
    (net (code "2") (name "+3V3_NFC") (class "Default")
      (node (ref "C511") (pin "2") (pinfunction "2_2") (pintype "passive"))
      (node (ref "J31") (pin "1") (pinfunction "1_1") (pintype "passive"))
      (node (ref "J54") (pin "2") (pinfunction "2_2") (pintype "passive"))
      (node (ref "Q56") (pin "2") (pinfunction "2_2") (pintype "passive"))
    )
    (net (code "3") (name "+3V3_US") (class "Default")
      (node (ref "C24") (pin "2") (pinfunction "2_2") (pintype "passive"))
      (node (ref "C55") (pin "2") (pinfunction "2_2") (pintype "passive"))
      (node (ref "J52") (pin "2") (pinfunction "2_2") (pintype "passive"))
      (node (ref "Q54") (pin "2") (pinfunction "2_2") (pintype "passive"))
      (node (ref "U24") (pin "5") (pinfunction "VCC_5") (pintype "passive"))
    )
    (net (code "4") (name "+5V") (class "Default")
      (node (ref "C51") (pin "2") (pinfunction "2_2") (pintype "passive"))
      (node (ref "C57") (pin "2") (pinfunction "2_2") (pintype "passive"))
      (node (ref "J12") (pin "2") (pinfunction "2_2") (pintype "passive"))
      (node (ref "J12") (pin "4") (pinfunction "4_4") (pintype "passive"))
      (node (ref "J12") (pin "6") (pinfunction "6_6") (pintype "passive"))
      (node (ref "J51") (pin "1") (pinfunction "1_1") (pintype "passive"))
      (node (ref "J53") (pin "1") (pinfunction "1_1") (pintype "passive"))
      (node (ref "Q53") (pin "3") (pinfunction "3_3") (pintype "passive"))
      (node (ref "Q55") (pin "3") (pinfunction "3_3") (pintype "passive"))
      (node (ref "R41") (pin "2") (pinfunction "2_2") (pintype "passive"))
      (node (ref "R42") (pin "2") (pinfunction "2_2") (pintype "passive"))
      (node (ref "R43") (pin "2") (pinfunction "2_2") (pintype "passive"))
    )
    (net (code "5") (name "+5V_GSM") (class "Default")
      (node (ref "C11") (pin "2") (pinfunction "2_2") (pintype "passive"))
      (node (ref "C12") (pin "2") (pinfunction "2_2") (pintype "passive"))
      (node (ref "C13") (pin "2") (pinfunction "2_2") (pintype "passive"))
      (node (ref "C58") (pin "2") (pinfunction "2_2") (pintype "passive"))
      (node (ref "J13") (pin "1") (pinfunction "1_1") (pintype "passive"))
      (node (ref "J53") (pin "2") (pinfunction "2_2") (pintype "passive"))
      (node (ref "Q55") (pin "2") (pinfunction "2_2") (pintype "passive"))
    )
    (net (code "6") (name "+5V_US") (class "Default")
      (node (ref "C21") (pin "2") (pinfunction "2_2") (pintype "passive"))
      (node (ref "C22") (pin "2") (pinfunction "2_2") (pintype "passive"))
      (node (ref "C23") (pin "2") (pinfunction "2_2") (pintype "passive"))
      (node (ref "C52") (pin "2") (pinfunction "2_2") (pintype "passive"))
      (node (ref "J21") (pin "1") (pinfunction "1_1") (pintype "passive"))
      (node (ref "J22") (pin "1") (pinfunction "1_1") (pintype "passive"))
      (node (ref "J23") (pin "1") (pinfunction "1_1") (pintype "passive"))
      (node (ref "J24") (pin "1") (pinfunction "1_1") (pintype "passive"))
      (node (ref "J25") (pin "1") (pinfunction "1_1") (pintype "passive"))
      (node (ref "J51") (pin "2") (pinfunction "2_2") (pintype "passive"))
      (node (ref "Q53") (pin "2") (pinfunction "2_2") (pintype "passive"))
      (node (ref "U21") (pin "16") (pinfunction "VDD_16") (pintype "power_in"))
      (node (ref "U22") (pin "16") (pinfunction "VDD_16") (pintype "power_in"))
      (node (ref "U23") (pin "5") (pinfunction "VCC_5") (pintype "passive"))
    )
    (net (code "7") (name "+5V_ZYBO") (class "Default")
      (node (ref "C621") (pin "2") (pinfunction "2_2") (pintype "passive"))
      (node (ref "C622") (pin "2") (pinfunction "2_2") (pintype "passive"))
      (node (ref "J01") (pin "1") (pinfunction "1_1") (pintype "passive"))
      (node (ref "L61") (pin "2") (pinfunction "2_2") (pintype "passive"))
      (node (ref "R44") (pin "2") (pinfunction "2_2") (pintype "passive"))
      (node (ref "R61") (pin "2") (pinfunction "2_2") (pintype "passive"))
    )
    (net (code "8") (name "+12V") (class "Default")
      (node (ref "C61") (pin "2") (pinfunction "2_2") (pintype "passive"))
      (node (ref "J12") (pin "14") (pinfunction "14_14") (pintype "passive"))
      (node (ref "J12") (pin "16") (pinfunction "16_16") (pintype "passive"))
      (node (ref "J12") (pin "18") (pinfunction "18_18") (pintype "passive"))
      (node (ref "R31") (pin "2") (pinfunction "2_2") (pintype "passive"))
      (node (ref "R516") (pin "1") (pinfunction "1_1") (pintype "passive"))
      (node (ref "R52") (pin "1") (pinfunction "1_1") (pintype "passive"))
      (node (ref "R523") (pin "1") (pinfunction "1_1") (pintype "passive"))
      (node (ref "R59") (pin "1") (pinfunction "1_1") (pintype "passive"))
      (node (ref "U61") (pin "3") (pinfunction "3_3") (pintype "passive"))
    )
    (net (code "9") (name "/BALISE_I2C_SCL") (class "Default")
      (node (ref "J33") (pin "4") (pinfunction "4_4") (pintype "passive"))
      (node (ref "J34") (pin "2") (pinfunction "2_2") (pintype "passive"))
    )
    (net (code "10") (name "/BALISE_I2C_SDA") (class "Default")
      (node (ref "J33") (pin "3") (pinfunction "3_3") (pintype "passive"))
      (node (ref "J34") (pin "9") (pinfunction "9_9") (pintype "passive"))
    )
    (net (code "11") (name "/BAT_ALERT") (class "Default")
      (node (ref "J14") (pin "1") (pinfunction "1_1") (pintype "passive"))
      (node (ref "R47") (pin "1") (pinfunction "1_1") (pintype "passive"))
    )
    (net (code "12") (name "/BAT_I2C_SCL") (class "Default")
      (node (ref "J14") (pin "3") (pinfunction "3_3") (pintype "passive"))
      (node (ref "U31") (pin "5") (pinfunction "SCL_5") (pintype "input"))
    )
    (net (code "13") (name "/BAT_I2C_SDA") (class "Default")
      (node (ref "J14") (pin "9") (pinfunction "9_9") (pintype "passive"))
      (node (ref "U31") (pin "6") (pinfunction "SDA_6") (pintype "bidirectional"))
    )
    (net (code "14") (name "/GSM_RST") (class "Default")
      (node (ref "J13") (pin "7") (pinfunction "7_7") (pintype "passive"))
      (node (ref "J14") (pin "8") (pinfunction "8_8") (pintype "passive"))
    )
    (net (code "15") (name "/GSM_UART_RXD") (class "Default")
      (node (ref "J13") (pin "5") (pinfunction "5_5") (pintype "passive"))
      (node (ref "J14") (pin "2") (pinfunction "2_2") (pintype "passive"))
    )
    (net (code "16") (name "/GSM_UART_TXD") (class "Default")
      (node (ref "J13") (pin "4") (pinfunction "4_4") (pintype "passive"))
      (node (ref "J14") (pin "7") (pinfunction "7_7") (pintype "passive"))
    )
    (net (code "17") (name "/HOLO_LED_DEBUG") (class "Default")
      (node (ref "J11") (pin "16") (pinfunction "16_16") (pintype "passive"))
      (node (ref "R46") (pin "1") (pinfunction "1_1") (pintype "passive"))
    )
    (net (code "18") (name "/HOLO_LED_PWR") (class "Default")
      (node (ref "J11") (pin "14") (pinfunction "14_14") (pintype "passive"))
      (node (ref "R45") (pin "1") (pinfunction "1_1") (pintype "passive"))
    )
    (net (code "19") (name "/HOLO_UART_RX") (class "Default")
      (node (ref "J11") (pin "1") (pinfunction "1_1") (pintype "passive"))
      (node (ref "J14") (pin "4") (pinfunction "4_4") (pintype "passive"))
    )
    (net (code "20") (name "/HOLO_UART_TX") (class "Default")
      (node (ref "J11") (pin "3") (pinfunction "3_3") (pintype "passive"))
      (node (ref "J14") (pin "10") (pinfunction "10_10") (pintype "passive"))
    )
    (net (code "21") (name "/IMU_I2C_SCL") (class "Default")
      (node (ref "J32") (pin "4") (pinfunction "4_4") (pintype "passive"))
      (node (ref "J34") (pin "3") (pinfunction "3_3") (pintype "passive"))
    )
    (net (code "22") (name "/IMU_I2C_SDA") (class "Default")
      (node (ref "J32") (pin "3") (pinfunction "3_3") (pintype "passive"))
      (node (ref "J34") (pin "4") (pinfunction "4_4") (pintype "passive"))
    )
    (net (code "23") (name "/NFC_FD") (class "Default")
      (node (ref "J31") (pin "3") (pinfunction "3_3") (pintype "passive"))
      (node (ref "J34") (pin "8") (pinfunction "8_8") (pintype "passive"))
    )
    (net (code "24") (name "/NFC_I2C_SCL") (class "Default")
      (node (ref "J31") (pin "5") (pinfunction "5_5") (pintype "passive"))
      (node (ref "J34") (pin "7") (pinfunction "7_7") (pintype "passive"))
    )
    (net (code "25") (name "/NFC_I2C_SDA") (class "Default")
      (node (ref "J31") (pin "4") (pinfunction "4_4") (pintype "passive"))
      (node (ref "J34") (pin "1") (pinfunction "1_1") (pintype "passive"))
    )
    (net (code "26") (name "/PWR_MGT_GSM") (class "Default")
      (node (ref "J26") (pin "4") (pinfunction "4_4") (pintype "passive"))
      (node (ref "R518") (pin "1") (pinfunction "1_1") (pintype "passive"))
    )
    (net (code "27") (name "/PWR_MGT_NFC") (class "Default")
      (node (ref "J26") (pin "10") (pinfunction "10_10") (pintype "passive"))
      (node (ref "R525") (pin "1") (pinfunction "1_1") (pintype "passive"))
    )
    (net (code "28") (name "/PWR_MGT_US") (class "Default")
      (node (ref "J26") (pin "9") (pinfunction "9_9") (pintype "passive"))
      (node (ref "R511") (pin "1") (pinfunction "1_1") (pintype "passive"))
      (node (ref "R54") (pin "1") (pinfunction "1_1") (pintype "passive"))
    )
    (net (code "29") (name "/US_1_ECHO_5V") (class "Default")
      (node (ref "J21") (pin "3") (pinfunction "3_3") (pintype "passive"))
      (node (ref "U22") (pin "12") (pinfunction "S3_12") (pintype "bidirectional"))
    )
    (net (code "30") (name "/US_1_TRIG_5V") (class "Default")
      (node (ref "J21") (pin "2") (pinfunction "2_2") (pintype "passive"))
      (node (ref "U21") (pin "12") (pinfunction "S3_12") (pintype "bidirectional"))
    )
    (net (code "31") (name "/US_2_ECHO_5V") (class "Default")
      (node (ref "J22") (pin "3") (pinfunction "3_3") (pintype "passive"))
      (node (ref "U22") (pin "13") (pinfunction "S0_13") (pintype "bidirectional"))
    )
    (net (code "32") (name "/US_2_TRIG_5V") (class "Default")
      (node (ref "J22") (pin "2") (pinfunction "2_2") (pintype "passive"))
      (node (ref "U21") (pin "13") (pinfunction "S0_13") (pintype "bidirectional"))
    )
    (net (code "33") (name "/US_3_ECHO_5V") (class "Default")
      (node (ref "J23") (pin "3") (pinfunction "3_3") (pintype "passive"))
      (node (ref "U22") (pin "14") (pinfunction "S1_14") (pintype "bidirectional"))
    )
    (net (code "34") (name "/US_3_TRIG_5V") (class "Default")
      (node (ref "J23") (pin "2") (pinfunction "2_2") (pintype "passive"))
      (node (ref "U21") (pin "14") (pinfunction "S1_14") (pintype "bidirectional"))
    )
    (net (code "35") (name "/US_4_ECHO_5V") (class "Default")
      (node (ref "J24") (pin "3") (pinfunction "3_3") (pintype "passive"))
      (node (ref "U22") (pin "15") (pinfunction "S2_15") (pintype "bidirectional"))
    )
    (net (code "36") (name "/US_4_TRIG_5V") (class "Default")
      (node (ref "J24") (pin "2") (pinfunction "2_2") (pintype "passive"))
      (node (ref "U21") (pin "15") (pinfunction "S2_15") (pintype "bidirectional"))
    )
    (net (code "37") (name "/US_5_ECHO_5V") (class "Default")
      (node (ref "J25") (pin "3") (pinfunction "3_3") (pintype "passive"))
      (node (ref "U22") (pin "1") (pinfunction "S4_1") (pintype "bidirectional"))
    )
    (net (code "38") (name "/US_5_TRIG_5V") (class "Default")
      (node (ref "J25") (pin "2") (pinfunction "2_2") (pintype "passive"))
      (node (ref "U21") (pin "1") (pinfunction "S4_1") (pintype "bidirectional"))
    )
    (net (code "39") (name "/US_ECHO_3V3") (class "Default")
      (node (ref "J26") (pin "8") (pinfunction "8_8") (pintype "passive"))
      (node (ref "R25") (pin "2") (pinfunction "2_2") (pintype "passive"))
    )
    (net (code "40") (name "/US_ECHO_5V") (class "Default")
      (node (ref "U22") (pin "3") (pinfunction "D_3") (pintype "bidirectional"))
      (node (ref "U24") (pin "1") (pinfunction "1_1") (pintype "passive"))
      (node (ref "U24") (pin "2") (pinfunction "2_2") (pintype "passive"))
    )
    (net (code "41") (name "/US_SEL_0") (class "Default")
      (node (ref "J26") (pin "1") (pinfunction "1_1") (pintype "passive"))
      (node (ref "R21") (pin "2") (pinfunction "2_2") (pintype "passive"))
    )
    (net (code "42") (name "/US_SEL_1") (class "Default")
      (node (ref "J26") (pin "2") (pinfunction "2_2") (pintype "passive"))
      (node (ref "R22") (pin "2") (pinfunction "2_2") (pintype "passive"))
    )
    (net (code "43") (name "/US_SEL_2") (class "Default")
      (node (ref "J26") (pin "3") (pinfunction "3_3") (pintype "passive"))
      (node (ref "R23") (pin "2") (pinfunction "2_2") (pintype "passive"))
    )
    (net (code "44") (name "/US_TRIG_3V3") (class "Default")
      (node (ref "J26") (pin "7") (pinfunction "7_7") (pintype "passive"))
      (node (ref "R24") (pin "1") (pinfunction "1_1") (pintype "passive"))
    )
    (net (code "45") (name "/US_TRIG_5V") (class "Default")
      (node (ref "U21") (pin "3") (pinfunction "D_3") (pintype "bidirectional"))
      (node (ref "U23") (pin "4") (pinfunction "4_4") (pintype "passive"))
    )
    (net (code "46") (name "GND") (class "Default")
      (node (ref "C11") (pin "1") (pinfunction "1_1") (pintype "passive"))
      (node (ref "C12") (pin "1") (pinfunction "1_1") (pintype "passive"))
      (node (ref "C13") (pin "1") (pinfunction "1_1") (pintype "passive"))
      (node (ref "C21") (pin "1") (pinfunction "1_1") (pintype "passive"))
      (node (ref "C22") (pin "1") (pinfunction "1_1") (pintype "passive"))
      (node (ref "C23") (pin "1") (pinfunction "1_1") (pintype "passive"))
      (node (ref "C24") (pin "1") (pinfunction "1_1") (pintype "passive"))
      (node (ref "C31") (pin "1") (pinfunction "1_1") (pintype "passive"))
      (node (ref "C32") (pin "1") (pinfunction "1_1") (pintype "passive"))
      (node (ref "C33") (pin "1") (pinfunction "1_1") (pintype "passive"))
      (node (ref "C34") (pin "1") (pinfunction "1_1") (pintype "passive"))
      (node (ref "C512") (pin "1") (pinfunction "1_1") (pintype "passive"))
      (node (ref "C53") (pin "1") (pinfunction "1_1") (pintype "passive"))
      (node (ref "C56") (pin "1") (pinfunction "1_1") (pintype "passive"))
      (node (ref "C59") (pin "1") (pinfunction "1_1") (pintype "passive"))
      (node (ref "C61") (pin "1") (pinfunction "1_1") (pintype "passive"))
      (node (ref "C621") (pin "1") (pinfunction "1_1") (pintype "passive"))
      (node (ref "C622") (pin "1") (pinfunction "1_1") (pintype "passive"))
      (node (ref "D4") (pin "1") (pinfunction "1_1") (pintype "passive"))
      (node (ref "J01") (pin "2") (pinfunction "2_2") (pintype "passive"))
      (node (ref "J01") (pin "3") (pinfunction "3_3") (pintype "passive"))
      (node (ref "J11") (pin "10") (pinfunction "10_10") (pintype "passive"))
      (node (ref "J11") (pin "12") (pinfunction "12_12") (pintype "passive"))
      (node (ref "J11") (pin "13") (pinfunction "13_13") (pintype "passive"))
      (node (ref "J11") (pin "15") (pinfunction "15_15") (pintype "passive"))
      (node (ref "J11") (pin "18") (pinfunction "18_18") (pintype "passive"))
      (node (ref "J11") (pin "20") (pinfunction "20_20") (pintype "passive"))
      (node (ref "J11") (pin "5") (pinfunction "5_5") (pintype "passive"))
      (node (ref "J11") (pin "7") (pinfunction "7_7") (pintype "passive"))
      (node (ref "J12") (pin "1") (pinfunction "1_1") (pintype "passive"))
      (node (ref "J12") (pin "10") (pinfunction "10_10") (pintype "passive"))
      (node (ref "J12") (pin "11") (pinfunction "11_11") (pintype "passive"))
      (node (ref "J12") (pin "12") (pinfunction "12_12") (pintype "passive"))
      (node (ref "J12") (pin "13") (pinfunction "13_13") (pintype "passive"))
      (node (ref "J12") (pin "15") (pinfunction "15_15") (pintype "passive"))
      (node (ref "J12") (pin "20") (pinfunction "20_20") (pintype "passive"))
      (node (ref "J12") (pin "3") (pinfunction "3_3") (pintype "passive"))
      (node (ref "J12") (pin "8") (pinfunction "8_8") (pintype "passive"))
      (node (ref "J13") (pin "2") (pinfunction "2_2") (pintype "passive"))
      (node (ref "J13") (pin "6") (pinfunction "6_6") (pintype "passive"))
      (node (ref "J14") (pin "11") (pinfunction "11_11") (pintype "passive"))
      (node (ref "J14") (pin "5") (pinfunction "5_5") (pintype "passive"))
      (node (ref "J21") (pin "4") (pinfunction "4_4") (pintype "passive"))
      (node (ref "J22") (pin "4") (pinfunction "4_4") (pintype "passive"))
      (node (ref "J23") (pin "4") (pinfunction "4_4") (pintype "passive"))
      (node (ref "J24") (pin "4") (pinfunction "4_4") (pintype "passive"))
      (node (ref "J25") (pin "4") (pinfunction "4_4") (pintype "passive"))
      (node (ref "J26") (pin "11") (pinfunction "11_11") (pintype "passive"))
      (node (ref "J26") (pin "5") (pinfunction "5_5") (pintype "passive"))
      (node (ref "J31") (pin "2") (pinfunction "2_2") (pintype "passive"))
      (node (ref "J31") (pin "6") (pinfunction "6_6") (pintype "passive"))
      (node (ref "J32") (pin "1") (pinfunction "1_1") (pintype "passive"))
      (node (ref "J33") (pin "2") (pinfunction "2_2") (pintype "passive"))
      (node (ref "J34") (pin "11") (pinfunction "11_11") (pintype "passive"))
      (node (ref "J34") (pin "5") (pinfunction "5_5") (pintype "passive"))
      (node (ref "Q41") (pin "2") (pinfunction "2_2") (pintype "passive"))
      (node (ref "Q42") (pin "2") (pinfunction "2_2") (pintype "passive"))
      (node (ref "Q43") (pin "2") (pinfunction "2_2") (pintype "passive"))
      (node (ref "R32") (pin "1") (pinfunction "1_1") (pintype "passive"))
      (node (ref "R513") (pin "1") (pinfunction "1_1") (pintype "passive"))
      (node (ref "R514") (pin "1") (pinfunction "1_1") (pintype "passive"))
      (node (ref "R520") (pin "1") (pinfunction "1_1") (pintype "passive"))
      (node (ref "R521") (pin "1") (pinfunction "1_1") (pintype "passive"))
      (node (ref "R527") (pin "1") (pinfunction "1_1") (pintype "passive"))
      (node (ref "R528") (pin "1") (pinfunction "1_1") (pintype "passive"))
      (node (ref "R56") (pin "1") (pinfunction "1_1") (pintype "passive"))
      (node (ref "R57") (pin "1") (pinfunction "1_1") (pintype "passive"))
      (node (ref "R62") (pin "1") (pinfunction "1_1") (pintype "passive"))
      (node (ref "U21") (pin "6") (pinfunction "~{EN}_6") (pintype "input"))
      (node (ref "U21") (pin "8") (pinfunction "GND_8") (pintype "power_in"))
      (node (ref "U22") (pin "6") (pinfunction "~{EN}_6") (pintype "input"))
      (node (ref "U22") (pin "8") (pinfunction "GND_8") (pintype "power_in"))
      (node (ref "U23") (pin "3") (pinfunction "GND_3") (pintype "passive"))
      (node (ref "U24") (pin "3") (pinfunction "GND_3") (pintype "passive"))
      (node (ref "U31") (pin "2") (pinfunction "GND_2") (pintype "power_in"))
      (node (ref "U61") (pin "1") (pinfunction "1_1") (pintype "passive"))
    )
    (net (code "47") (name "Net-(C63-Pad1)") (class "Default")
      (node (ref "C63") (pin "1") (pinfunction "1_1") (pintype "passive"))
      (node (ref "U61") (pin "4") (pinfunction "4_4") (pintype "passive"))
    )
    (net (code "48") (name "Net-(C63-Pad2)") (class "Default")
      (node (ref "C63") (pin "2") (pinfunction "2_2") (pintype "passive"))
      (node (ref "L61") (pin "1") (pinfunction "1_1") (pintype "passive"))
      (node (ref "U61") (pin "2") (pinfunction "2_2") (pintype "passive"))
    )
    (net (code "49") (name "Net-(D1-Pad1)") (class "Default")
      (node (ref "D1") (pin "1") (pinfunction "1_1") (pintype "passive"))
      (node (ref "Q41") (pin "3") (pinfunction "3_3") (pintype "passive"))
    )
    (net (code "50") (name "Net-(D1-Pad2)") (class "Default")
      (node (ref "D1") (pin "2") (pinfunction "2_2") (pintype "passive"))
      (node (ref "R41") (pin "1") (pinfunction "1_1") (pintype "passive"))
    )
    (net (code "51") (name "Net-(D2-Pad1)") (class "Default")
      (node (ref "D2") (pin "1") (pinfunction "1_1") (pintype "passive"))
      (node (ref "Q42") (pin "3") (pinfunction "3_3") (pintype "passive"))
    )
    (net (code "52") (name "Net-(D2-Pad2)") (class "Default")
      (node (ref "D2") (pin "2") (pinfunction "2_2") (pintype "passive"))
      (node (ref "R42") (pin "1") (pinfunction "1_1") (pintype "passive"))
    )
    (net (code "53") (name "Net-(D3-Pad1)") (class "Default")
      (node (ref "D3") (pin "1") (pinfunction "1_1") (pintype "passive"))
      (node (ref "Q43") (pin "3") (pinfunction "3_3") (pintype "passive"))
    )
    (net (code "54") (name "Net-(D3-Pad2)") (class "Default")
      (node (ref "D3") (pin "2") (pinfunction "2_2") (pintype "passive"))
      (node (ref "R43") (pin "1") (pinfunction "1_1") (pintype "passive"))
    )
    (net (code "55") (name "Net-(D4-Pad2)") (class "Default")
      (node (ref "D4") (pin "2") (pinfunction "2_2") (pintype "passive"))
      (node (ref "R44") (pin "1") (pinfunction "1_1") (pintype "passive"))
    )
    (net (code "56") (name "Net-(Q41-Pad1)") (class "Default")
      (node (ref "Q41") (pin "1") (pinfunction "1_1") (pintype "passive"))
      (node (ref "R45") (pin "2") (pinfunction "2_2") (pintype "passive"))
    )
    (net (code "57") (name "Net-(Q42-Pad1)") (class "Default")
      (node (ref "Q42") (pin "1") (pinfunction "1_1") (pintype "passive"))
      (node (ref "R46") (pin "2") (pinfunction "2_2") (pintype "passive"))
    )
    (net (code "58") (name "Net-(Q43-Pad1)") (class "Default")
      (node (ref "Q43") (pin "1") (pinfunction "1_1") (pintype "passive"))
      (node (ref "R47") (pin "2") (pinfunction "2_2") (pintype "passive"))
    )
    (net (code "59") (name "Net-(Q51A-B)") (class "Default")
      (node (ref "C53") (pin "2") (pinfunction "2_2") (pintype "passive"))
      (node (ref "Q51") (pin "2") (pinfunction "B_2") (pintype "passive"))
      (node (ref "R55") (pin "2") (pinfunction "2_2") (pintype "passive"))
      (node (ref "R56") (pin "2") (pinfunction "2_2") (pintype "passive"))
    )
    (net (code "60") (name "Net-(Q51A-C)") (class "Default")
      (node (ref "C51") (pin "1") (pinfunction "1_1") (pintype "passive"))
      (node (ref "C52") (pin "1") (pinfunction "1_1") (pintype "passive"))
      (node (ref "Q51") (pin "6") (pinfunction "C_6") (pintype "passive"))
      (node (ref "R51") (pin "1") (pinfunction "1_1") (pintype "passive"))
      (node (ref "R52") (pin "2") (pinfunction "2_2") (pintype "passive"))
    )
    (net (code "61") (name "Net-(Q51A-E)") (class "Default")
      (node (ref "Q51") (pin "1") (pinfunction "E_1") (pintype "passive"))
      (node (ref "R57") (pin "2") (pinfunction "2_2") (pintype "passive"))
    )
    (net (code "62") (name "Net-(Q51B-B)") (class "Default")
      (node (ref "C59") (pin "2") (pinfunction "2_2") (pintype "passive"))
      (node (ref "Q51") (pin "5") (pinfunction "B_5") (pintype "passive"))
      (node (ref "R519") (pin "2") (pinfunction "2_2") (pintype "passive"))
      (node (ref "R520") (pin "2") (pinfunction "2_2") (pintype "passive"))
    )
    (net (code "63") (name "Net-(Q51B-C)") (class "Default")
      (node (ref "C57") (pin "1") (pinfunction "1_1") (pintype "passive"))
      (node (ref "C58") (pin "1") (pinfunction "1_1") (pintype "passive"))
      (node (ref "Q51") (pin "3") (pinfunction "C_3") (pintype "passive"))
      (node (ref "R515") (pin "1") (pinfunction "1_1") (pintype "passive"))
      (node (ref "R516") (pin "2") (pinfunction "2_2") (pintype "passive"))
    )
    (net (code "64") (name "Net-(Q51B-E)") (class "Default")
      (node (ref "Q51") (pin "4") (pinfunction "E_4") (pintype "passive"))
      (node (ref "R521") (pin "2") (pinfunction "2_2") (pintype "passive"))
    )
    (net (code "65") (name "Net-(Q52A-B)") (class "Default")
      (node (ref "C56") (pin "2") (pinfunction "2_2") (pintype "passive"))
      (node (ref "Q52") (pin "2") (pinfunction "B_2") (pintype "passive"))
      (node (ref "R512") (pin "2") (pinfunction "2_2") (pintype "passive"))
      (node (ref "R513") (pin "2") (pinfunction "2_2") (pintype "passive"))
    )
    (net (code "66") (name "Net-(Q52A-C)") (class "Default")
      (node (ref "C54") (pin "1") (pinfunction "1_1") (pintype "passive"))
      (node (ref "C55") (pin "1") (pinfunction "1_1") (pintype "passive"))
      (node (ref "Q52") (pin "6") (pinfunction "C_6") (pintype "passive"))
      (node (ref "R58") (pin "1") (pinfunction "1_1") (pintype "passive"))
      (node (ref "R59") (pin "2") (pinfunction "2_2") (pintype "passive"))
    )
    (net (code "67") (name "Net-(Q52A-E)") (class "Default")
      (node (ref "Q52") (pin "1") (pinfunction "E_1") (pintype "passive"))
      (node (ref "R514") (pin "2") (pinfunction "2_2") (pintype "passive"))
    )
    (net (code "68") (name "Net-(Q52B-B)") (class "Default")
      (node (ref "C512") (pin "2") (pinfunction "2_2") (pintype "passive"))
      (node (ref "Q52") (pin "5") (pinfunction "B_5") (pintype "passive"))
      (node (ref "R526") (pin "2") (pinfunction "2_2") (pintype "passive"))
      (node (ref "R527") (pin "2") (pinfunction "2_2") (pintype "passive"))
    )
    (net (code "69") (name "Net-(Q52B-C)") (class "Default")
      (node (ref "C510") (pin "1") (pinfunction "1_1") (pintype "passive"))
      (node (ref "C511") (pin "1") (pinfunction "1_1") (pintype "passive"))
      (node (ref "Q52") (pin "3") (pinfunction "C_3") (pintype "passive"))
      (node (ref "R522") (pin "1") (pinfunction "1_1") (pintype "passive"))
      (node (ref "R523") (pin "2") (pinfunction "2_2") (pintype "passive"))
    )
    (net (code "70") (name "Net-(Q52B-E)") (class "Default")
      (node (ref "Q52") (pin "4") (pinfunction "E_4") (pintype "passive"))
      (node (ref "R528") (pin "2") (pinfunction "2_2") (pintype "passive"))
    )
    (net (code "71") (name "Net-(Q53-Pad1)") (class "Default")
      (node (ref "Q53") (pin "1") (pinfunction "1_1") (pintype "passive"))
      (node (ref "R51") (pin "2") (pinfunction "2_2") (pintype "passive"))
    )
    (net (code "72") (name "Net-(Q54-Pad1)") (class "Default")
      (node (ref "Q54") (pin "1") (pinfunction "1_1") (pintype "passive"))
      (node (ref "R58") (pin "2") (pinfunction "2_2") (pintype "passive"))
    )
    (net (code "73") (name "Net-(Q55-Pad1)") (class "Default")
      (node (ref "Q55") (pin "1") (pinfunction "1_1") (pintype "passive"))
      (node (ref "R515") (pin "2") (pinfunction "2_2") (pintype "passive"))
    )
    (net (code "74") (name "Net-(Q56-Pad1)") (class "Default")
      (node (ref "Q56") (pin "1") (pinfunction "1_1") (pintype "passive"))
      (node (ref "R522") (pin "2") (pinfunction "2_2") (pintype "passive"))
    )
    (net (code "75") (name "Net-(R24-Pad2)") (class "Default")
      (node (ref "R24") (pin "2") (pinfunction "2_2") (pintype "passive"))
      (node (ref "U23") (pin "1") (pinfunction "1_1") (pintype "passive"))
      (node (ref "U23") (pin "2") (pinfunction "2_2") (pintype "passive"))
    )
    (net (code "76") (name "Net-(R25-Pad1)") (class "Default")
      (node (ref "R25") (pin "1") (pinfunction "1_1") (pintype "passive"))
      (node (ref "U24") (pin "4") (pinfunction "4_4") (pintype "passive"))
    )
    (net (code "77") (name "Net-(R53-Pad1)") (class "Default")
      (node (ref "R53") (pin "1") (pinfunction "1_1") (pintype "passive"))
      (node (ref "R54") (pin "2") (pinfunction "2_2") (pintype "passive"))
      (node (ref "R55") (pin "1") (pinfunction "1_1") (pintype "passive"))
    )
    (net (code "78") (name "Net-(R61-Pad1)") (class "Default")
      (node (ref "R61") (pin "1") (pinfunction "1_1") (pintype "passive"))
      (node (ref "R62") (pin "2") (pinfunction "2_2") (pintype "passive"))
      (node (ref "U61") (pin "6") (pinfunction "6_6") (pintype "passive"))
    )
    (net (code "79") (name "Net-(R510-Pad1)") (class "Default")
      (node (ref "R510") (pin "1") (pinfunction "1_1") (pintype "passive"))
      (node (ref "R511") (pin "2") (pinfunction "2_2") (pintype "passive"))
      (node (ref "R512") (pin "1") (pinfunction "1_1") (pintype "passive"))
    )
    (net (code "80") (name "Net-(R517-Pad1)") (class "Default")
      (node (ref "R517") (pin "1") (pinfunction "1_1") (pintype "passive"))
      (node (ref "R518") (pin "2") (pinfunction "2_2") (pintype "passive"))
      (node (ref "R519") (pin "1") (pinfunction "1_1") (pintype "passive"))
    )
    (net (code "81") (name "Net-(R524-Pad1)") (class "Default")
      (node (ref "R524") (pin "1") (pinfunction "1_1") (pintype "passive"))
      (node (ref "R525") (pin "2") (pinfunction "2_2") (pintype "passive"))
      (node (ref "R526") (pin "1") (pinfunction "1_1") (pintype "passive"))
    )
    (net (code "82") (name "Net-(U21-A0)") (class "Default")
      (node (ref "R21") (pin "1") (pinfunction "1_1") (pintype "passive"))
      (node (ref "U21") (pin "11") (pinfunction "A0_11") (pintype "input"))
      (node (ref "U22") (pin "11") (pinfunction "A0_11") (pintype "input"))
    )
    (net (code "83") (name "Net-(U21-A1)") (class "Default")
      (node (ref "R22") (pin "1") (pinfunction "1_1") (pintype "passive"))
      (node (ref "U21") (pin "10") (pinfunction "A1_10") (pintype "input"))
      (node (ref "U22") (pin "10") (pinfunction "A1_10") (pintype "input"))
    )
    (net (code "84") (name "Net-(U21-A2)") (class "Default")
      (node (ref "R23") (pin "1") (pinfunction "1_1") (pintype "passive"))
      (node (ref "U21") (pin "9") (pinfunction "A2_9") (pintype "input"))
      (node (ref "U22") (pin "9") (pinfunction "A2_9") (pintype "input"))
    )
    (net (code "85") (name "Net-(U31-VIN)") (class "Default")
      (node (ref "C31") (pin "2") (pinfunction "2_2") (pintype "passive"))
      (node (ref "R31") (pin "1") (pinfunction "1_1") (pintype "passive"))
      (node (ref "R32") (pin "2") (pinfunction "2_2") (pintype "passive"))
      (node (ref "U31") (pin "3") (pinfunction "VIN_3") (pintype "input"))
    )
    (net (code "86") (name "unconnected-(J11-Pad2)") (class "Default")
      (node (ref "J11") (pin "2") (pinfunction "2_2") (pintype "passive+no_connect"))
    )
    (net (code "87") (name "unconnected-(J11-Pad4)") (class "Default")
      (node (ref "J11") (pin "4") (pinfunction "4_4") (pintype "passive+no_connect"))
    )
    (net (code "88") (name "unconnected-(J11-Pad6)") (class "Default")
      (node (ref "J11") (pin "6") (pinfunction "6_6") (pintype "passive+no_connect"))
    )
    (net (code "89") (name "unconnected-(J11-Pad8)") (class "Default")
      (node (ref "J11") (pin "8") (pinfunction "8_8") (pintype "passive+no_connect"))
    )
    (net (code "90") (name "unconnected-(J11-Pad9)") (class "Default")
      (node (ref "J11") (pin "9") (pinfunction "9_9") (pintype "passive+no_connect"))
    )
    (net (code "91") (name "unconnected-(J11-Pad11)") (class "Default")
      (node (ref "J11") (pin "11") (pinfunction "11_11") (pintype "passive+no_connect"))
    )
    (net (code "92") (name "unconnected-(J11-Pad17)") (class "Default")
      (node (ref "J11") (pin "17") (pinfunction "17_17") (pintype "passive+no_connect"))
    )
    (net (code "93") (name "unconnected-(J11-Pad19)") (class "Default")
      (node (ref "J11") (pin "19") (pinfunction "19_19") (pintype "passive+no_connect"))
    )
    (net (code "94") (name "unconnected-(J14-Pad6)") (class "Default")
      (node (ref "J14") (pin "6") (pinfunction "6_6") (pintype "passive+no_connect"))
    )
    (net (code "95") (name "unconnected-(J14-Pad12)") (class "Default")
      (node (ref "J14") (pin "12") (pinfunction "12_12") (pintype "passive+no_connect"))
    )
    (net (code "96") (name "unconnected-(J26-Pad6)") (class "Default")
      (node (ref "J26") (pin "6") (pinfunction "6_6") (pintype "passive+no_connect"))
    )
    (net (code "97") (name "unconnected-(J26-Pad12)") (class "Default")
      (node (ref "J26") (pin "12") (pinfunction "12_12") (pintype "passive+no_connect"))
    )
    (net (code "98") (name "unconnected-(J34-Pad6)") (class "Default")
      (node (ref "J34") (pin "6") (pinfunction "6_6") (pintype "passive+no_connect"))
    )
    (net (code "99") (name "unconnected-(J34-Pad10)") (class "Default")
      (node (ref "J34") (pin "10") (pinfunction "10_10") (pintype "passive+no_connect"))
    )
    (net (code "100") (name "unconnected-(J34-Pad12)") (class "Default")
      (node (ref "J34") (pin "12") (pinfunction "12_12") (pintype "passive+no_connect"))
    )
    (net (code "101") (name "unconnected-(U21-NC-Pad7)") (class "Default")
      (node (ref "U21") (pin "7") (pinfunction "NC_7") (pintype "power_in+no_connect"))
    )
    (net (code "102") (name "unconnected-(U21-S5-Pad5)") (class "Default")
      (node (ref "U21") (pin "5") (pinfunction "S5_5") (pintype "bidirectional+no_connect"))
    )
    (net (code "103") (name "unconnected-(U21-S6-Pad2)") (class "Default")
      (node (ref "U21") (pin "2") (pinfunction "S6_2") (pintype "bidirectional+no_connect"))
    )
    (net (code "104") (name "unconnected-(U21-S7-Pad4)") (class "Default")
      (node (ref "U21") (pin "4") (pinfunction "S7_4") (pintype "bidirectional+no_connect"))
    )
    (net (code "105") (name "unconnected-(U22-NC-Pad7)") (class "Default")
      (node (ref "U22") (pin "7") (pinfunction "NC_7") (pintype "power_in+no_connect"))
    )
    (net (code "106") (name "unconnected-(U22-S5-Pad5)") (class "Default")
      (node (ref "U22") (pin "5") (pinfunction "S5_5") (pintype "bidirectional+no_connect"))
    )
    (net (code "107") (name "unconnected-(U22-S6-Pad2)") (class "Default")
      (node (ref "U22") (pin "2") (pinfunction "S6_2") (pintype "bidirectional+no_connect"))
    )
    (net (code "108") (name "unconnected-(U22-S7-Pad4)") (class "Default")
      (node (ref "U22") (pin "4") (pinfunction "S7_4") (pintype "bidirectional+no_connect"))
    )
    (net (code "109") (name "unconnected-(U31-ADDR-Pad4)") (class "Default")
      (node (ref "U31") (pin "4") (pinfunction "ADDR_4") (pintype "input+no_connect"))
    )
    (net (code "110") (name "unconnected-(U61-Pad5)") (class "Default")
      (node (ref "U61") (pin "5") (pinfunction "5_5") (pintype "passive+no_connect"))
    )
  )
)
